# EEZ_DIB_DCP405_r2B5.net
KiCad netlist of a schematic drawn in EAGLE
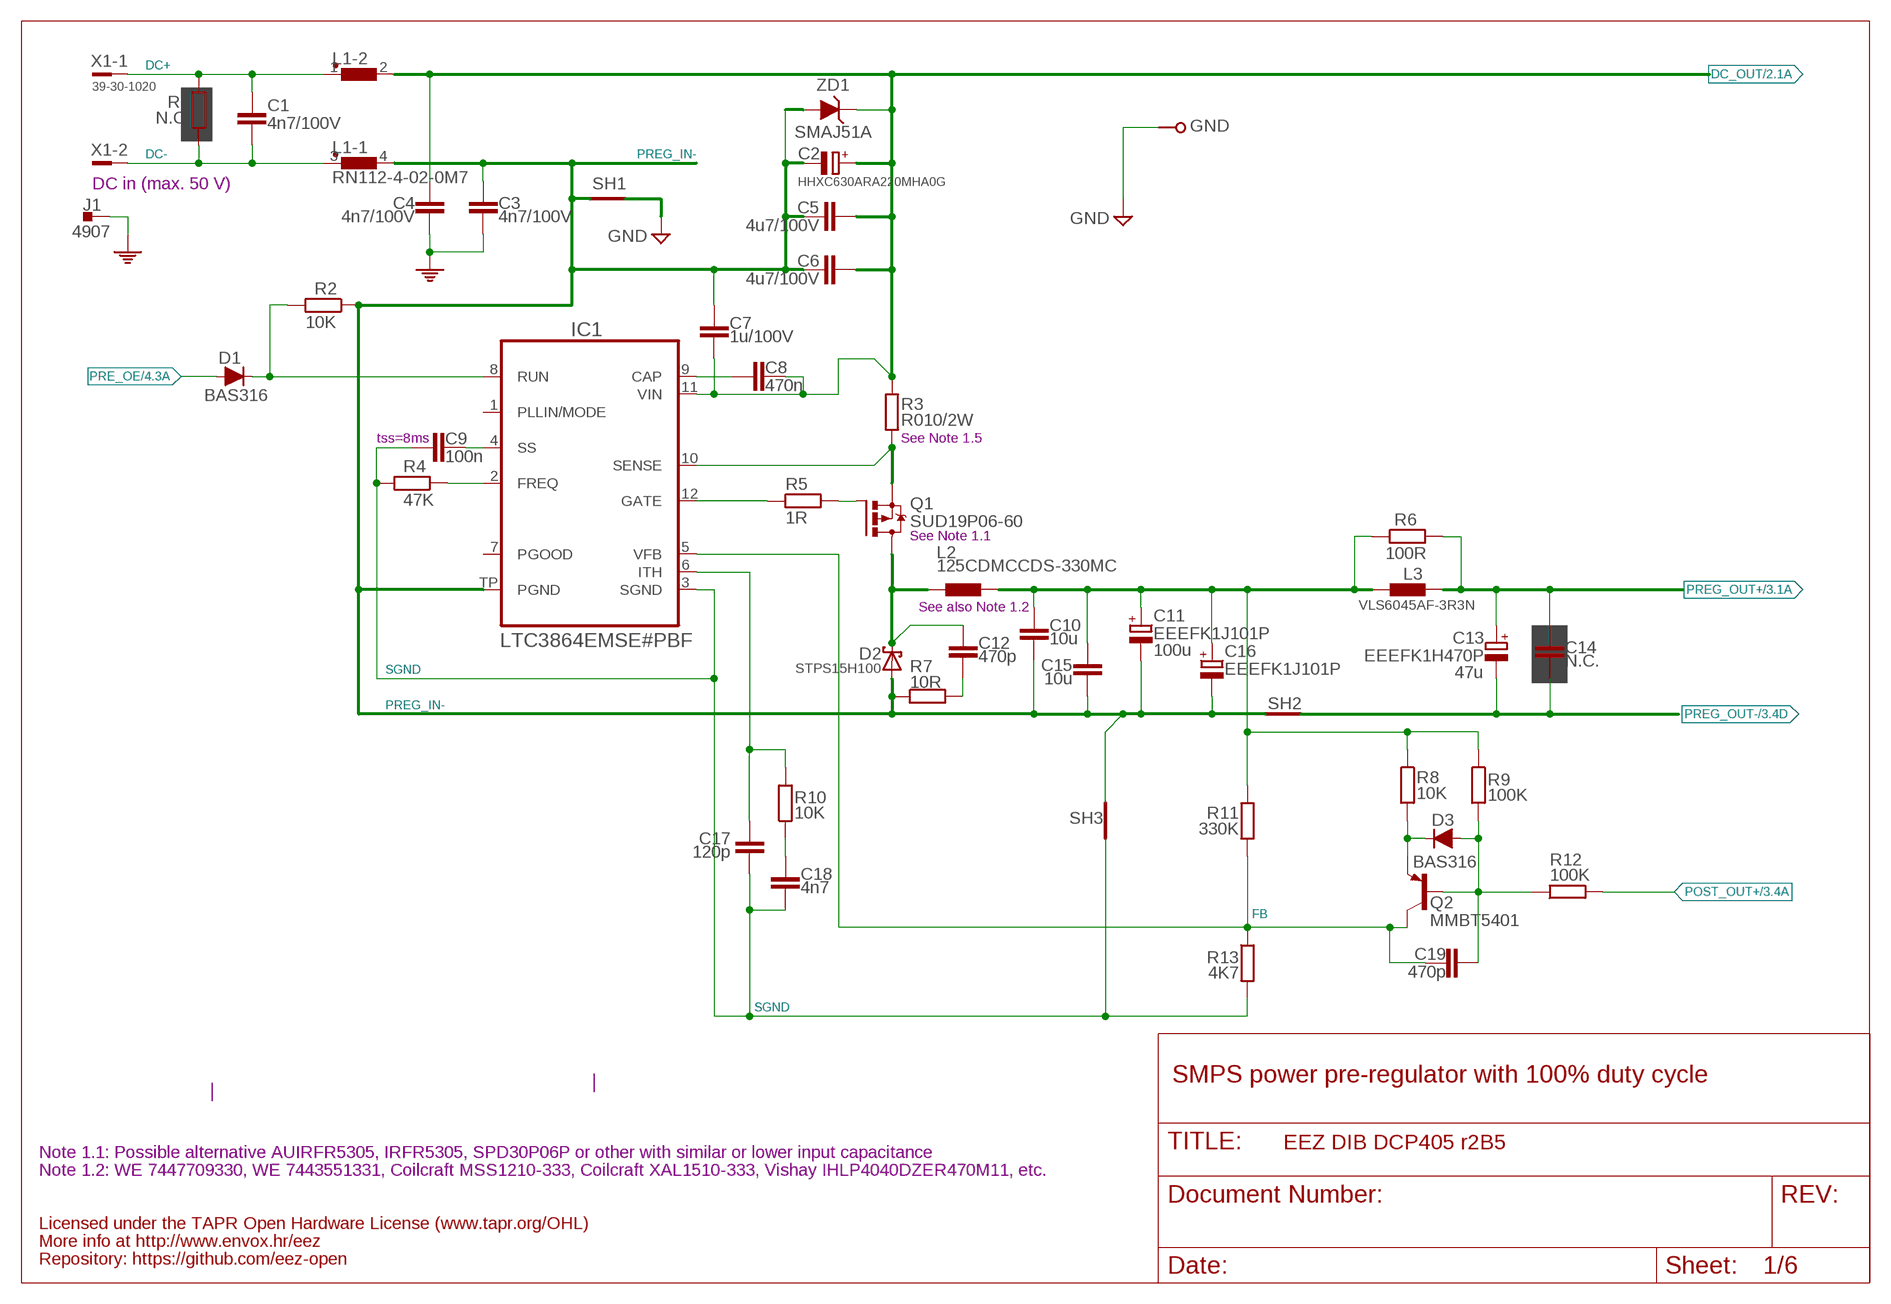
[diagram p0: schematic, sheet 1]
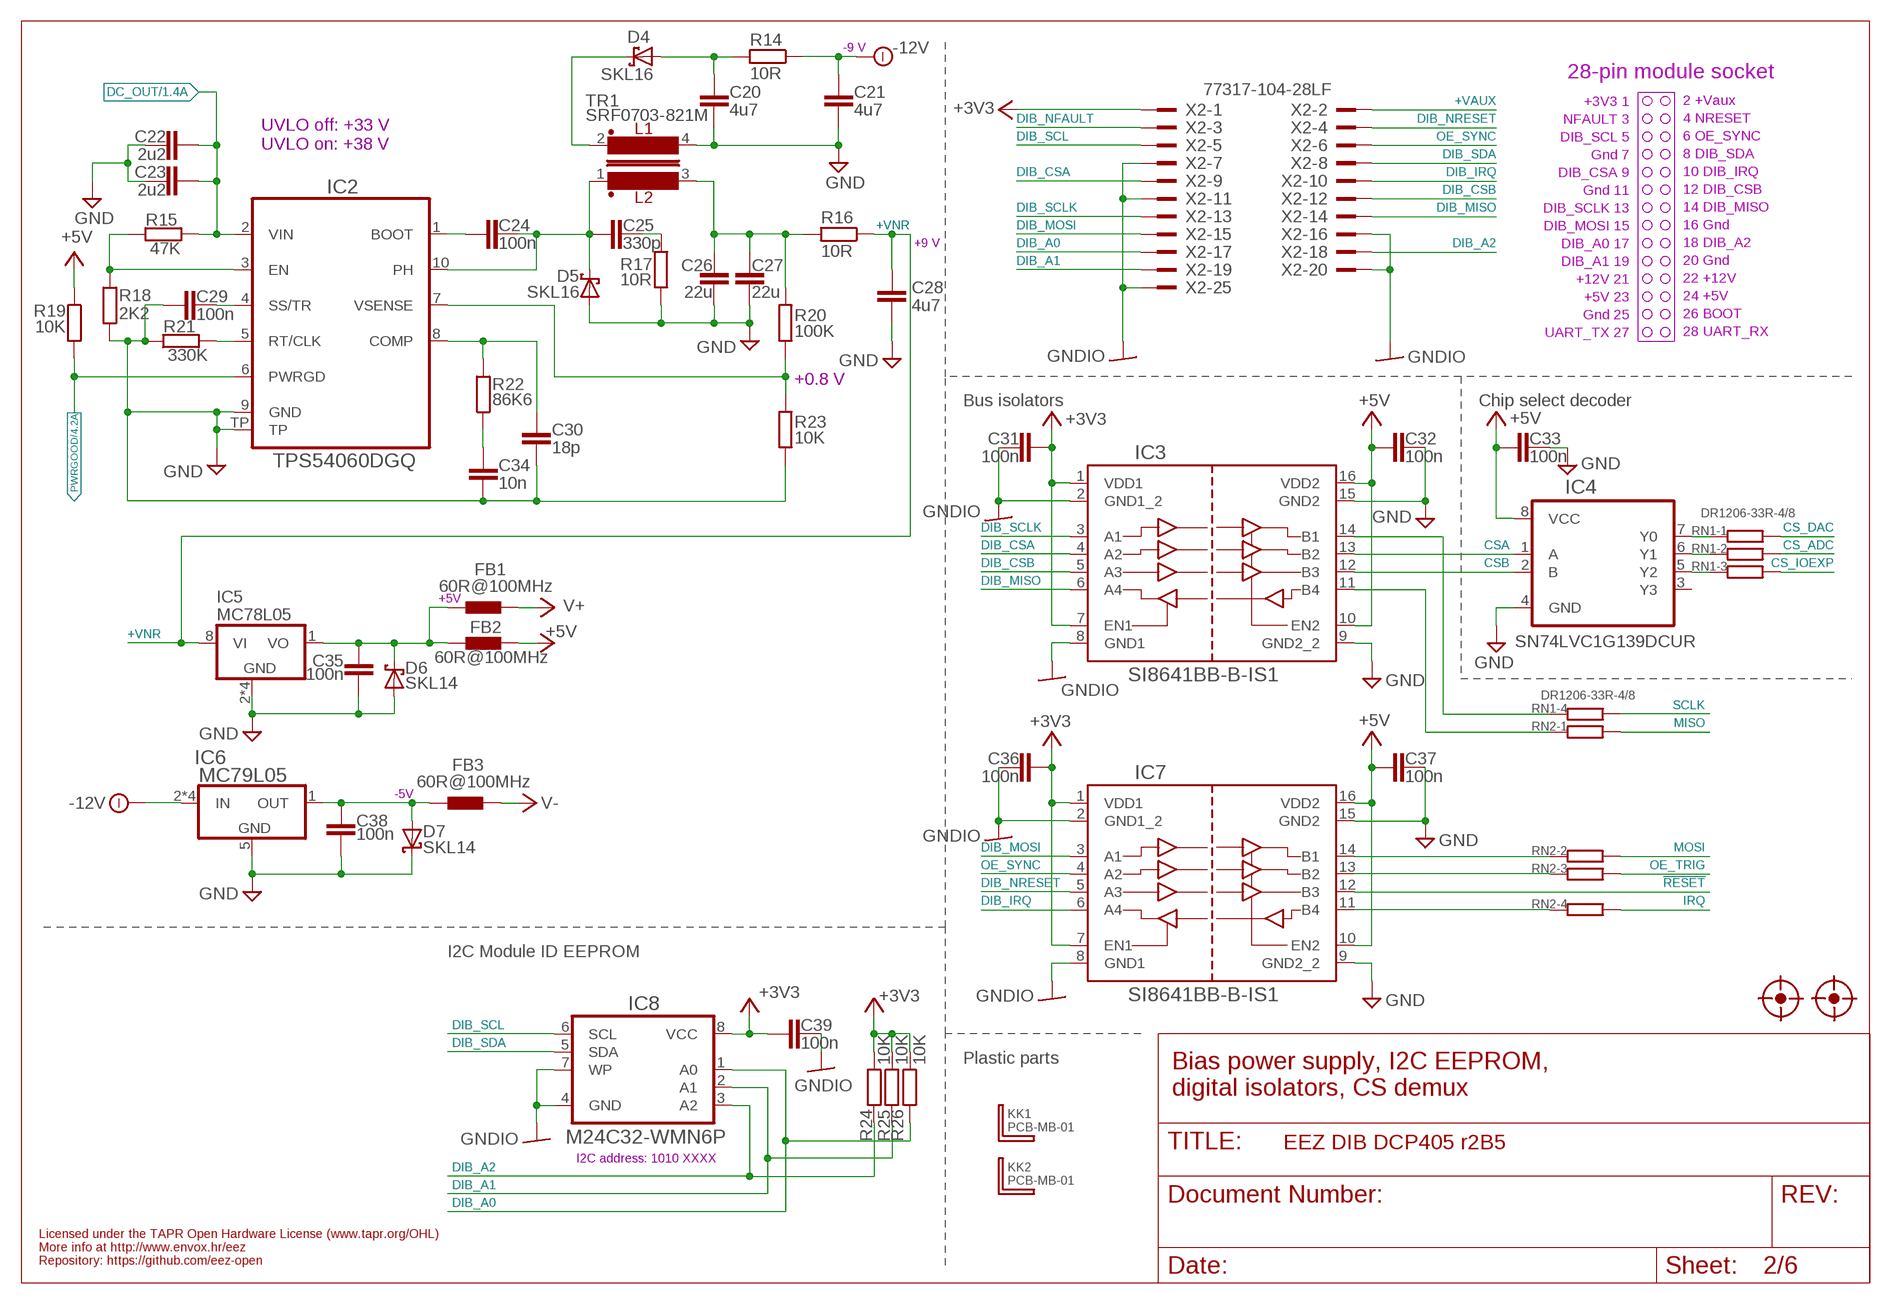
[diagram p1: schematic, sheet 2]
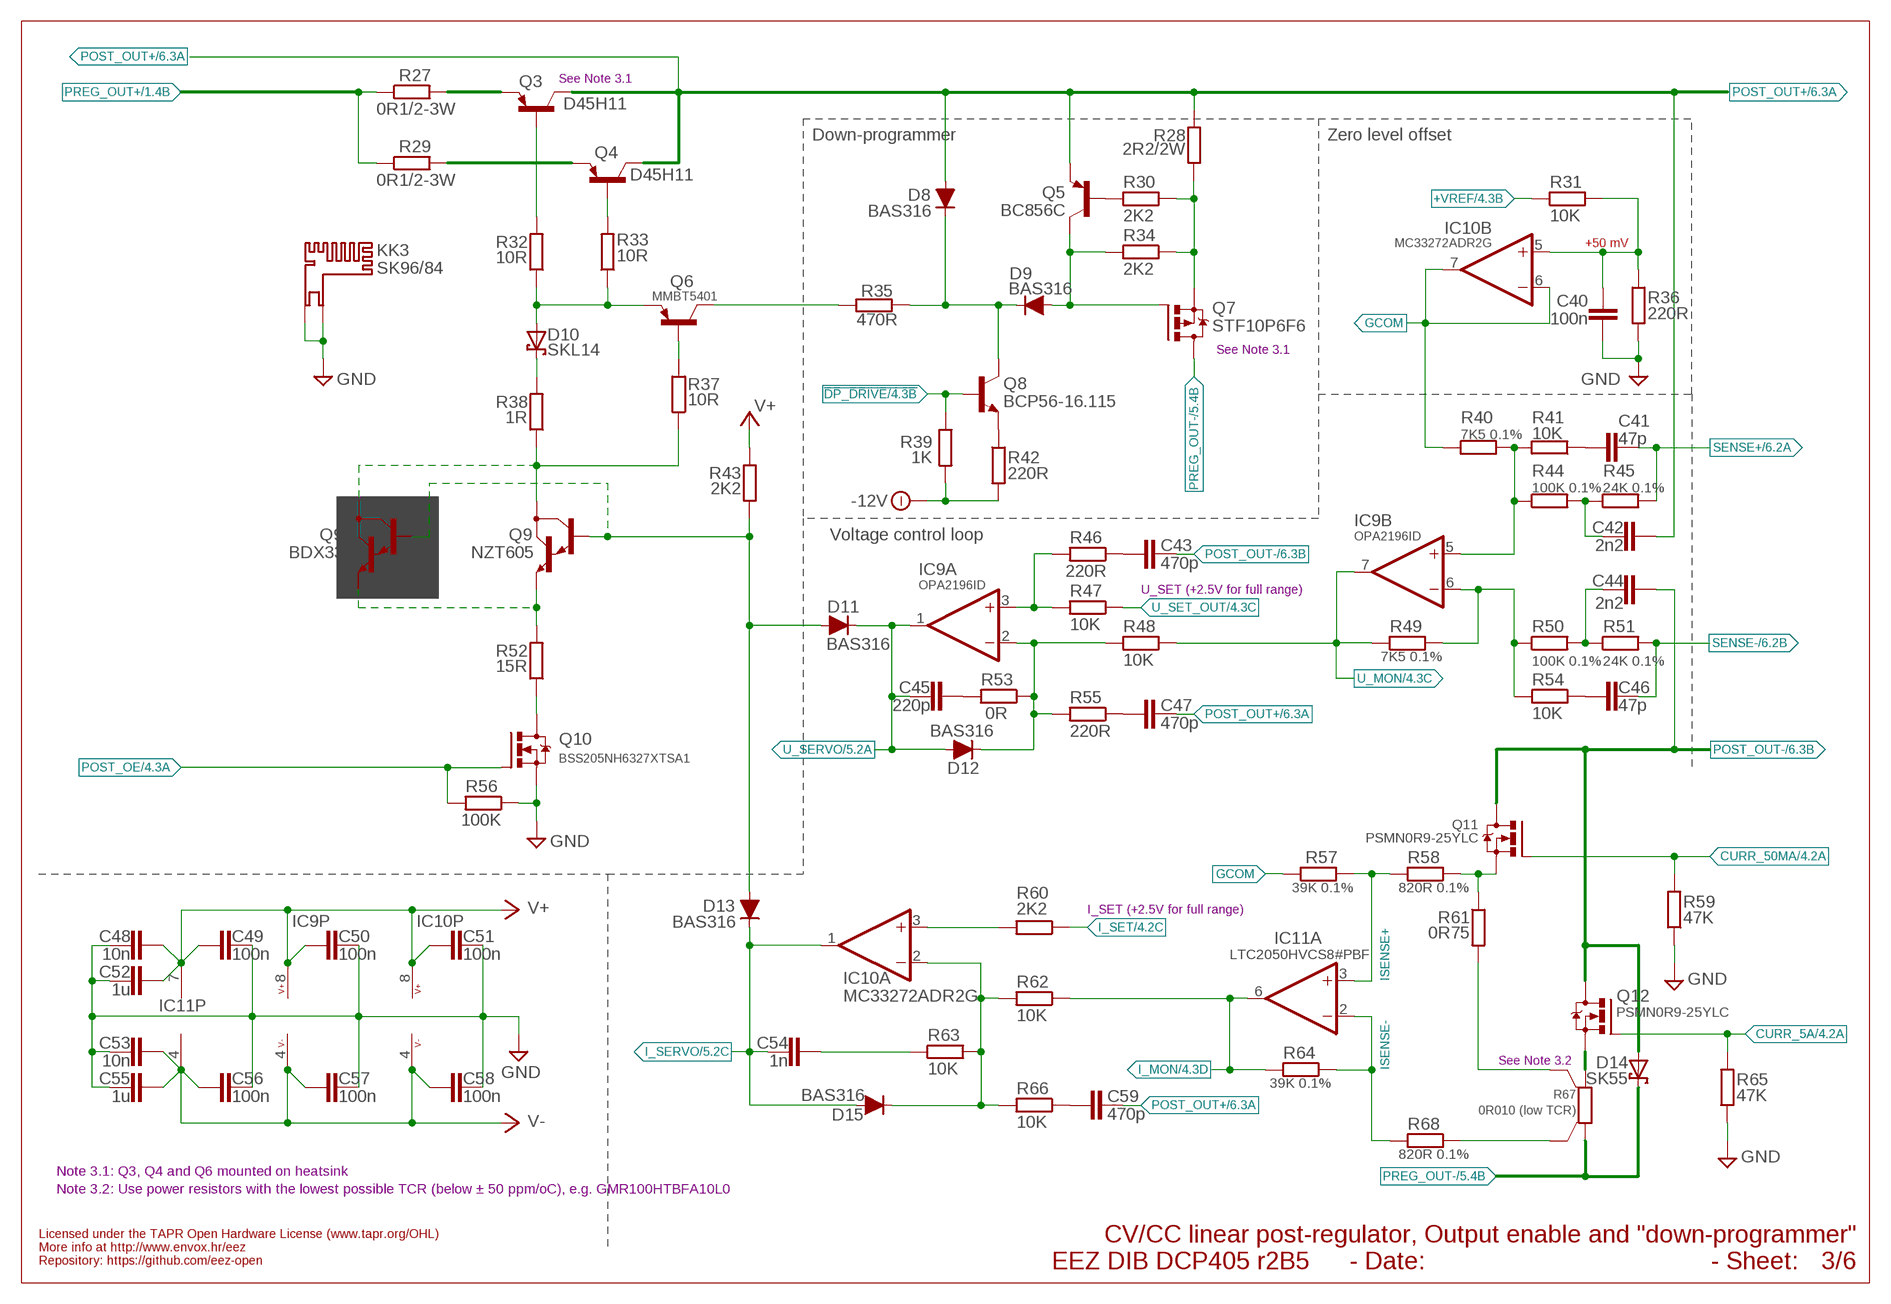
[diagram p2: schematic, sheet 3]
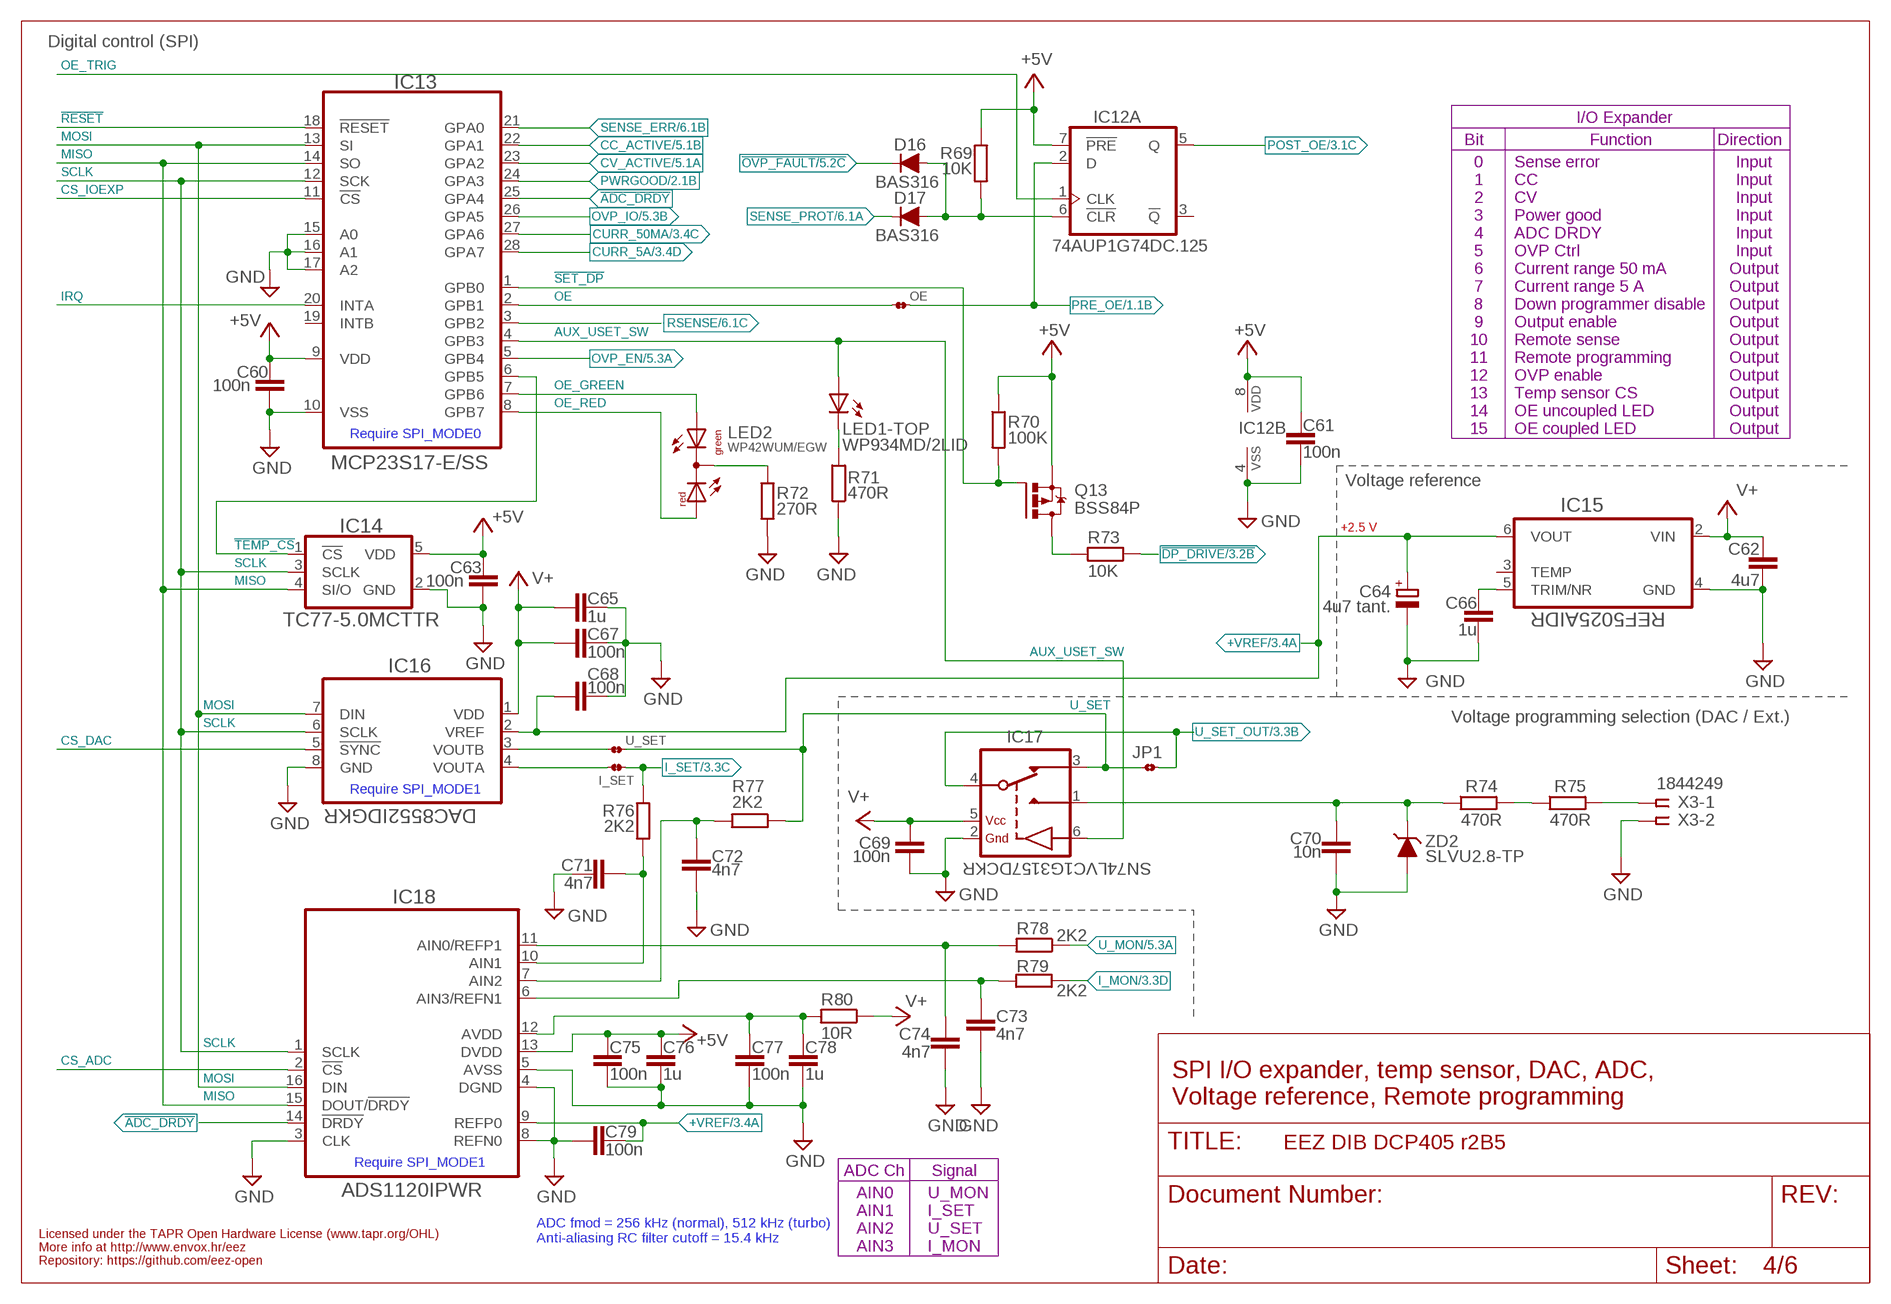
[diagram p3: schematic, sheet 4]
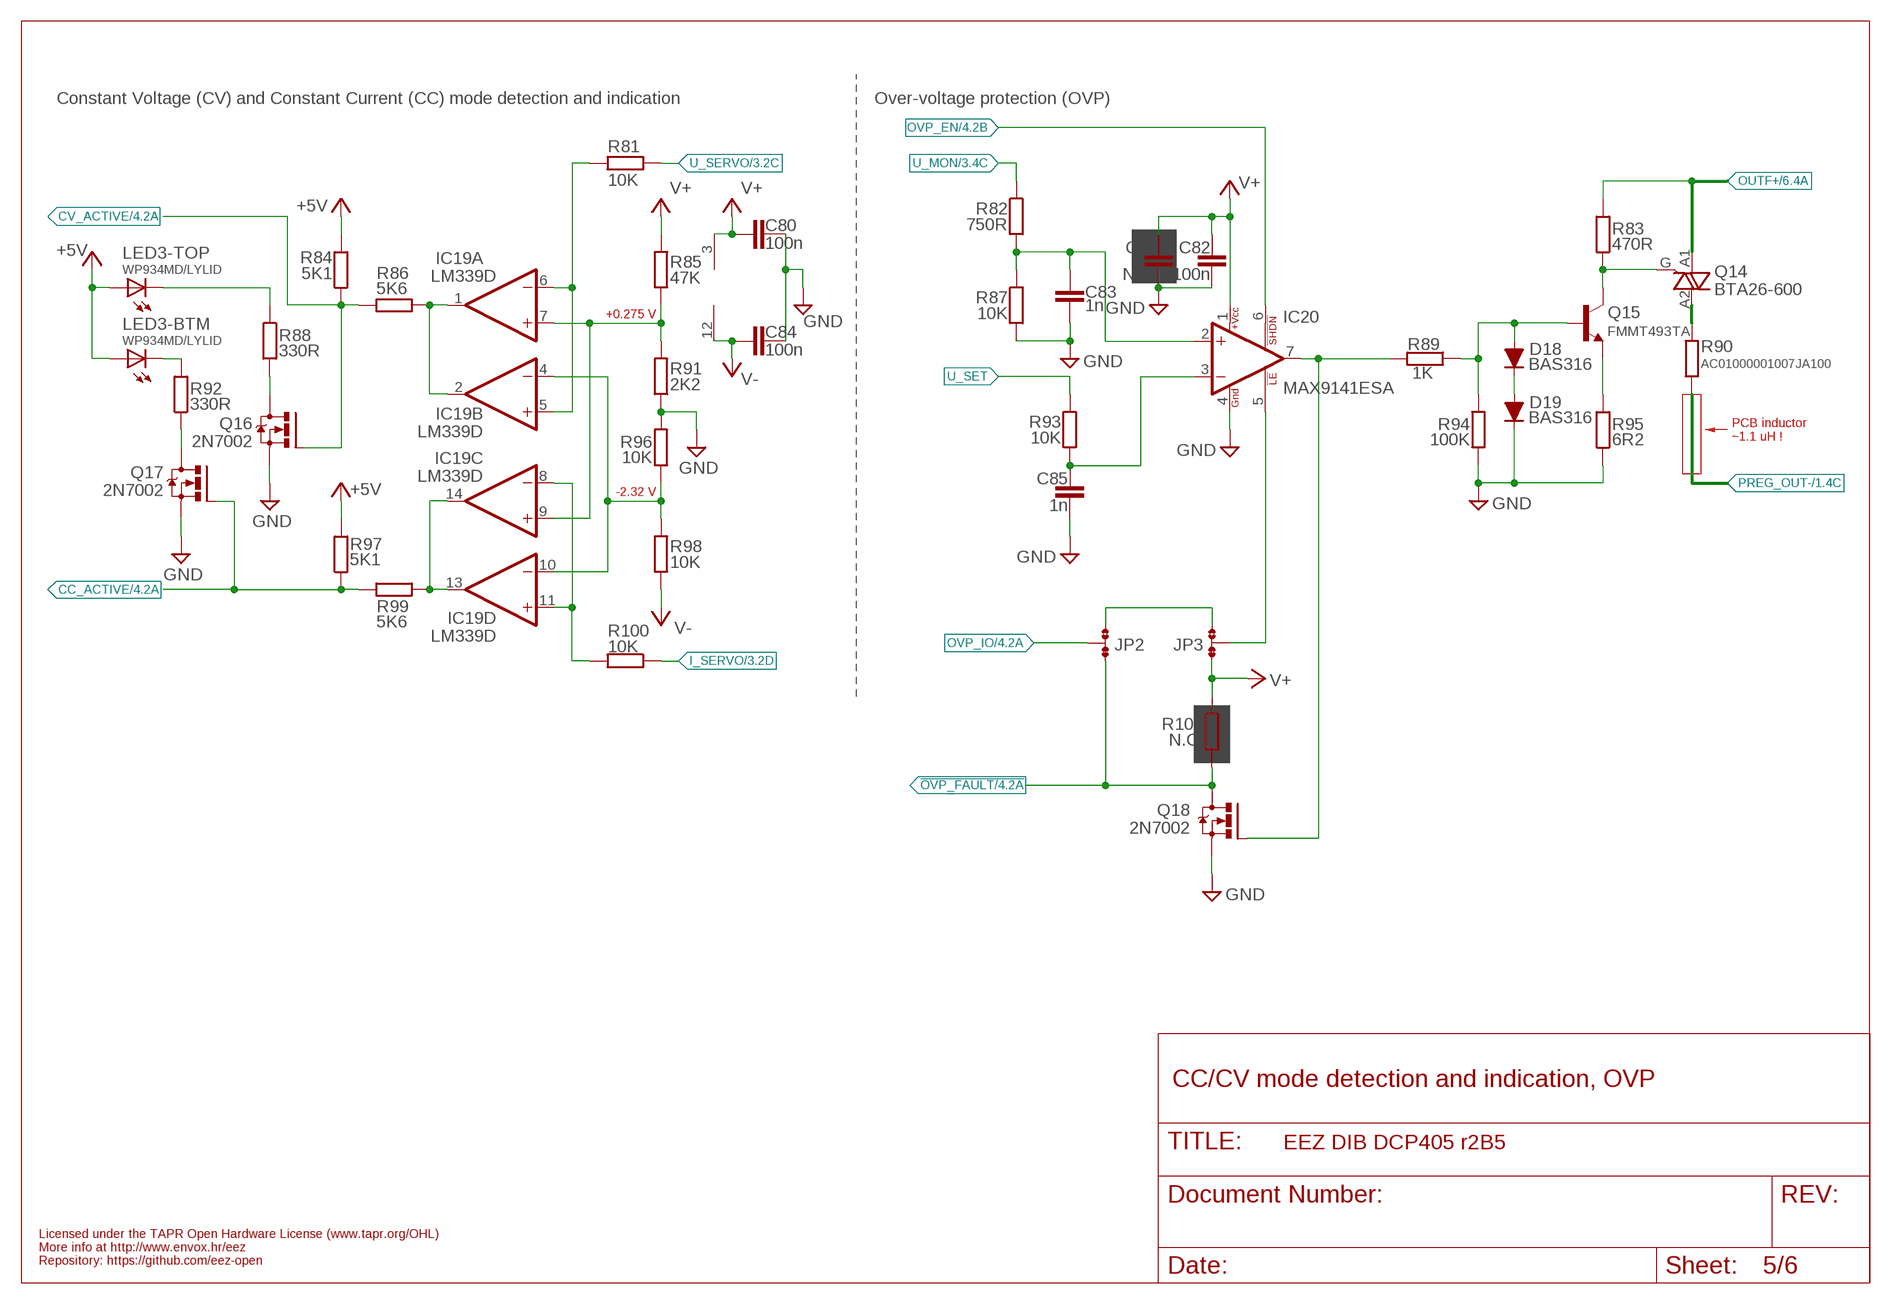
[diagram p4: schematic, sheet 5]
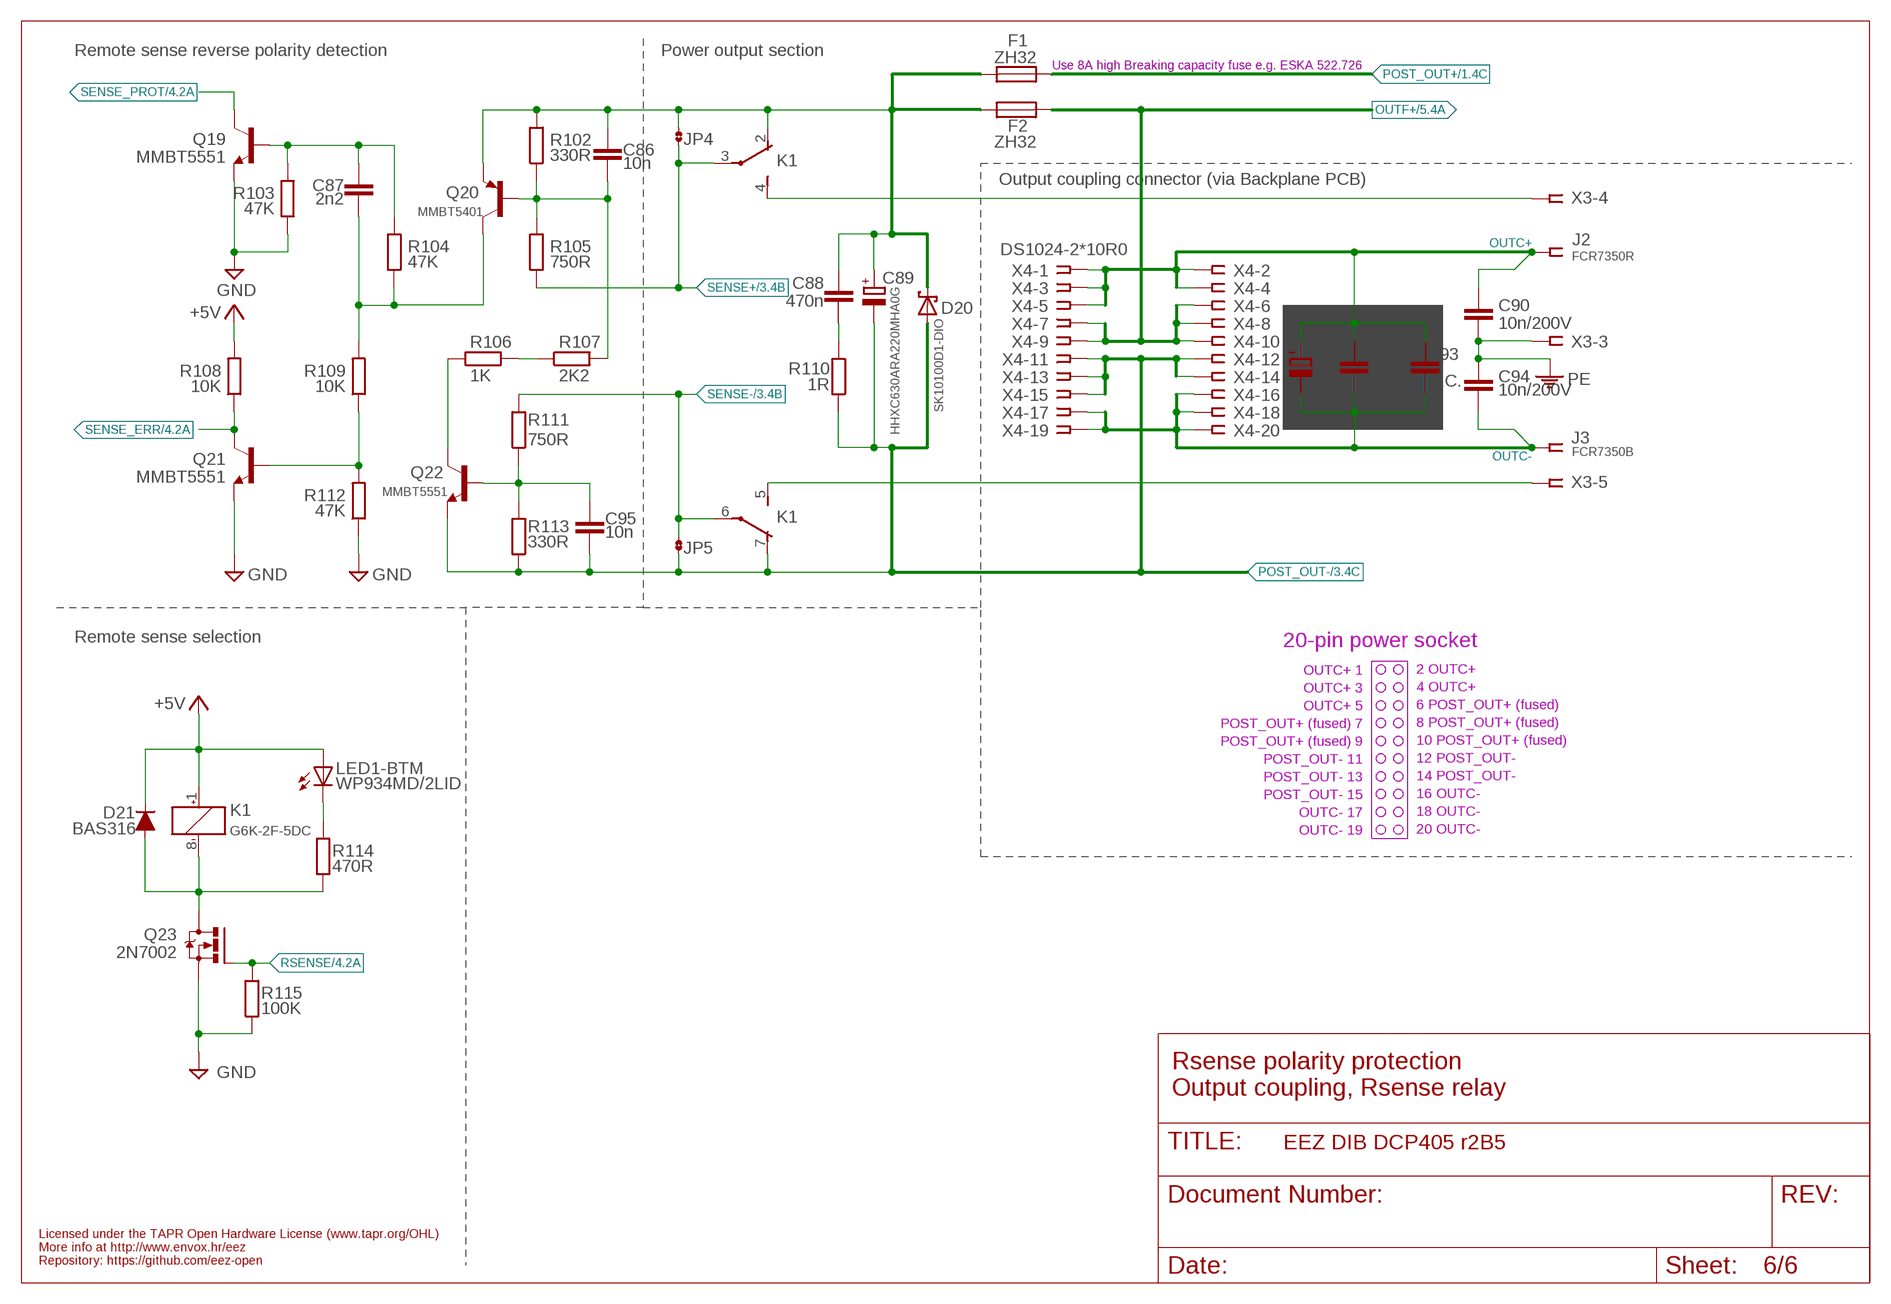
[diagram p5: schematic, sheet 6]

(export (version "E")
  (design (tool "Eeschema 10.0.6"))
  (components
    (comp (ref "C60")
      (value "100n")
      (footprint "eagle-import:C0603")
      (libsource (lib "eagle-import") (part "C-EUC0603"))
    )
    (comp (ref "C61")
      (value "100n")
      (footprint "eagle-import:C0603")
      (libsource (lib "eagle-import") (part "C-EUC0603"))
    )
    (comp (ref "C62")
      (value "4u7")
      (footprint "eagle-import:C1206")
      (libsource (lib "eagle-import") (part "C-EUC1206"))
    )
    (comp (ref "C63")
      (value "100n")
      (footprint "eagle-import:C0603")
      (libsource (lib "eagle-import") (part "C-EUC0603"))
    )
    (comp (ref "C64")
      (value "4u7 tant.")
      (footprint "eagle-import:EC1206")
      (libsource (lib "eagle-import") (part "ECAP1206"))
    )
    (comp (ref "C65")
      (value "1u")
      (footprint "eagle-import:C0805")
      (libsource (lib "eagle-import") (part "C-EUC0805"))
    )
    (comp (ref "C66")
      (value "1u")
      (footprint "eagle-import:C0805")
      (libsource (lib "eagle-import") (part "C-EUC0805"))
    )
    (comp (ref "C67")
      (value "100n")
      (footprint "eagle-import:C0603")
      (libsource (lib "eagle-import") (part "C-EUC0603"))
    )
    (comp (ref "C68")
      (value "100n")
      (footprint "eagle-import:C0603")
      (libsource (lib "eagle-import") (part "C-EUC0603"))
    )
    (comp (ref "C69")
      (value "100n")
      (footprint "eagle-import:C0603")
      (libsource (lib "eagle-import") (part "C-EUC0603"))
    )
    (comp (ref "C70")
      (value "10n")
      (footprint "eagle-import:C0805")
      (libsource (lib "eagle-import") (part "C-EUC0805"))
    )
    (comp (ref "C71")
      (value "4n7")
      (footprint "eagle-import:C0805")
      (libsource (lib "eagle-import") (part "C-EUC0805"))
    )
    (comp (ref "C72")
      (value "4n7")
      (footprint "eagle-import:C0805")
      (libsource (lib "eagle-import") (part "C-EUC0805"))
    )
    (comp (ref "C73")
      (value "4n7")
      (footprint "eagle-import:C0805")
      (libsource (lib "eagle-import") (part "C-EUC0805"))
    )
    (comp (ref "C74")
      (value "4n7")
      (footprint "eagle-import:C0805")
      (libsource (lib "eagle-import") (part "C-EUC0805"))
    )
    (comp (ref "C75")
      (value "100n")
      (footprint "eagle-import:C0603")
      (libsource (lib "eagle-import") (part "C-EUC0603"))
    )
    (comp (ref "C76")
      (value "1u")
      (footprint "eagle-import:C0805")
      (libsource (lib "eagle-import") (part "C-EUC0805"))
    )
    (comp (ref "C77")
      (value "100n")
      (footprint "eagle-import:C0603")
      (libsource (lib "eagle-import") (part "C-EUC0603"))
    )
    (comp (ref "C78")
      (value "1u")
      (footprint "eagle-import:C0805")
      (libsource (lib "eagle-import") (part "C-EUC0805"))
    )
    (comp (ref "C79")
      (value "100n")
      (footprint "eagle-import:C0603")
      (libsource (lib "eagle-import") (part "C-EUC0603"))
    )
    (comp (ref "D16")
      (value "BAS316")
      (footprint "eagle-import:SOD323-R")
      (libsource (lib "eagle-import") (part "DIODESOD323R"))
    )
    (comp (ref "D17")
      (value "BAS316")
      (footprint "eagle-import:SOD323-R")
      (libsource (lib "eagle-import") (part "DIODESOD323R"))
    )
    (comp (ref "IC12")
      (value "74AUP1G74DC.125")
      (footprint "eagle-import:DCU8")
      (libsource (lib "eagle-import") (part "SN74LVC1G74DCTR-VSSOP"))
    )
    (comp (ref "IC13")
      (value "MCP23S17-E/SS")
      (footprint "eagle-import:SOP65P780X200-28N")
      (libsource (lib "eagle-import") (part "MCP23S17-E/SSSSOP"))
    )
    (comp (ref "IC14")
      (value "TC77-5.0MCTTR")
      (footprint "eagle-import:SOT23-5")
      (libsource (lib "eagle-import") (part "TC77"))
    )
    (comp (ref "IC15")
      (value "REF5025AIDR")
      (footprint "eagle-import:SOIC127P600X175-8N")
      (libsource (lib "eagle-import") (part "REF50XX"))
    )
    (comp (ref "IC16")
      (value "DAC8552IDGKR")
      (footprint "eagle-import:DGK8-M")
      (libsource (lib "eagle-import") (part "DAC8552_DGK_8M"))
    )
    (comp (ref "IC17")
      (value "SN74LVC1G3157DCKR")
      (footprint "eagle-import:SOT65P210X110-6N")
      (libsource (lib "eagle-import") (part "SN74LVC1G3157-DCK"))
    )
    (comp (ref "IC18")
      (value "ADS1120IPWR")
      (footprint "eagle-import:PW(R-PDSO-G16)")
      (libsource (lib "eagle-import") (part "ADS1120TSSOP-16"))
    )
    (comp (ref "I_SET")
      (value "JP2-NOCUT")
      (footprint "eagle-import:JP2-NOCUT")
      (libsource (lib "eagle-import") (part "JP2-NOCUT"))
    )
    (comp (ref "JP1")
      (value "JP2-CUT")
      (footprint "eagle-import:JP2-CUT")
      (libsource (lib "eagle-import") (part "JP2-CUT"))
    )
    (comp (ref "LED1")
      (value "WP934MD/2LID")
      (footprint "eagle-import:WP934MD")
      (libsource (lib "eagle-import") (part "WP934MD/2LID"))
    )
    (comp (ref "LED2")
      (value "WP42WUM/EGW")
      (footprint "eagle-import:L-42WUM-1EGWT")
      (libsource (lib "eagle-import") (part "LED_L-42WUM/1EGWT"))
    )
    (comp (ref "OE")
      (value "JP2-NOCUT")
      (footprint "eagle-import:JP2-NOCUT")
      (libsource (lib "eagle-import") (part "JP2-NOCUT"))
    )
    (comp (ref "Q13")
      (value "BSS84P")
      (footprint "eagle-import:SOT95P237X112-3N")
      (fields (field (name "MPN") "IRLML2246TRPBF"))
      (libsource (lib "eagle-import") (part "IRLML2246TRPBF"))
    )
    (comp (ref "R69")
      (value "10K")
      (footprint "eagle-import:R0805")
      (libsource (lib "eagle-import") (part "R-EU_R0805"))
    )
    (comp (ref "R70")
      (value "100K")
      (footprint "eagle-import:R0805")
      (libsource (lib "eagle-import") (part "R-EU_R0805"))
    )
    (comp (ref "R71")
      (value "470R")
      (footprint "eagle-import:R0805")
      (libsource (lib "eagle-import") (part "R-EU_R0805"))
    )
    (comp (ref "R72")
      (value "270R")
      (footprint "eagle-import:R0805")
      (libsource (lib "eagle-import") (part "R-EU_R0805"))
    )
    (comp (ref "R73")
      (value "10K")
      (footprint "eagle-import:R0805")
      (libsource (lib "eagle-import") (part "R-EU_R0805"))
    )
    (comp (ref "R74")
      (value "470R")
      (footprint "eagle-import:R0805")
      (libsource (lib "eagle-import") (part "R-EU_R0805"))
    )
    (comp (ref "R75")
      (value "470R")
      (footprint "eagle-import:R0805")
      (libsource (lib "eagle-import") (part "R-EU_R0805"))
    )
    (comp (ref "R76")
      (value "2K2")
      (footprint "eagle-import:R0805")
      (libsource (lib "eagle-import") (part "R-EU_R0805"))
    )
    (comp (ref "R77")
      (value "2K2")
      (footprint "eagle-import:R0805")
      (libsource (lib "eagle-import") (part "R-EU_R0805"))
    )
    (comp (ref "R78")
      (value "2K2")
      (footprint "eagle-import:R0805")
      (libsource (lib "eagle-import") (part "R-EU_R0805"))
    )
    (comp (ref "R79")
      (value "2K2")
      (footprint "eagle-import:R0805")
      (libsource (lib "eagle-import") (part "R-EU_R0805"))
    )
    (comp (ref "R80")
      (value "10R")
      (footprint "eagle-import:R1206")
      (libsource (lib "eagle-import") (part "R-EU_R1206"))
    )
    (comp (ref "U_SET")
      (value "JP2-NOCUT")
      (footprint "eagle-import:JP2-NOCUT")
      (libsource (lib "eagle-import") (part "JP2-NOCUT"))
    )
    (comp (ref "X3")
      (value "1844249")
      (footprint "eagle-import:MC1,5_5-G-3,5")
      (libsource (lib "eagle-import") (part "MC1,5/5-G-3,5"))
    )
    (comp (ref "ZD2")
      (value "SLVU2.8-TP")
      (footprint "eagle-import:SOT23")
      (libsource (lib "eagle-import") (part "SLVU2.8"))
    )
    (comp (ref "C1")
      (value "4n7/100V")
      (footprint "eagle-import:C1206")
      (libsource (lib "eagle-import") (part "C-EUC1206"))
    )
    (comp (ref "C2")
      (value "HHXC630ARA220MHA0G")
      (footprint "eagle-import:CAPAE830X1050N")
      (libsource (lib "eagle-import") (part "ECAPSMD8.3MM/HA0"))
    )
    (comp (ref "C3")
      (value "4n7/100V")
      (footprint "eagle-import:C1206")
      (libsource (lib "eagle-import") (part "C-EUC1206"))
    )
    (comp (ref "C4")
      (value "4n7/100V")
      (footprint "eagle-import:C1206")
      (libsource (lib "eagle-import") (part "C-EUC1206"))
    )
    (comp (ref "C5")
      (value "4u7/100V")
      (footprint "eagle-import:C1210")
      (libsource (lib "eagle-import") (part "C-EUC1210"))
    )
    (comp (ref "C6")
      (value "4u7/100V")
      (footprint "eagle-import:C1210")
      (libsource (lib "eagle-import") (part "C-EUC1210"))
    )
    (comp (ref "C7")
      (value "1u/100V")
      (footprint "eagle-import:C1206")
      (libsource (lib "eagle-import") (part "C-EUC1206"))
    )
    (comp (ref "C8")
      (value "470n")
      (footprint "eagle-import:C0805")
      (libsource (lib "eagle-import") (part "C-EUC0805"))
    )
    (comp (ref "C9")
      (value "100n")
      (footprint "eagle-import:C0603")
      (libsource (lib "eagle-import") (part "C-EUC0603"))
    )
    (comp (ref "C10")
      (value "10u")
      (footprint "eagle-import:C1210")
      (libsource (lib "eagle-import") (part "C-EUC1210"))
    )
    (comp (ref "C11")
      (value "EEEFK1J101P")
      (footprint "eagle-import:CAPAE1030X1050N")
      (libsource (lib "eagle-import") (part "ECAP10X10"))
    )
    (comp (ref "C12")
      (value "470p")
      (footprint "eagle-import:C0805")
      (libsource (lib "eagle-import") (part "C-EUC0805"))
    )
    (comp (ref "C13")
      (value "EEEFK1H470P")
      (footprint "eagle-import:CAPAE830X1050N")
      (libsource (lib "eagle-import") (part "ECAPSMD8.3MM/HA0"))
    )
    (comp (ref "C14")
      (value "N.C.")
      (footprint "eagle-import:C0805")
      (libsource (lib "eagle-import") (part "C-EUC0805"))
    )
    (comp (ref "C15")
      (value "10u")
      (footprint "eagle-import:C1210")
      (libsource (lib "eagle-import") (part "C-EUC1210"))
    )
    (comp (ref "C16")
      (value "EEEFK1J101P")
      (footprint "eagle-import:CAPAE1030X1050N")
      (libsource (lib "eagle-import") (part "ECAP10X10"))
    )
    (comp (ref "C17")
      (value "120p")
      (footprint "eagle-import:C0805")
      (libsource (lib "eagle-import") (part "C-EUC0805"))
    )
    (comp (ref "C18")
      (value "4n7")
      (footprint "eagle-import:C0805")
      (libsource (lib "eagle-import") (part "C-EUC0805"))
    )
    (comp (ref "C19")
      (value "470p")
      (footprint "eagle-import:C0805")
      (libsource (lib "eagle-import") (part "C-EUC0805"))
    )
    (comp (ref "D1")
      (value "BAS316")
      (footprint "eagle-import:SOD323-R")
      (libsource (lib "eagle-import") (part "DIODESOD323R"))
    )
    (comp (ref "D2")
      (value "STPS15H100")
      (footprint "eagle-import:TO252-L")
      (libsource (lib "eagle-import") (part "SCHOTTKY-DUAL_A_L"))
    )
    (comp (ref "D3")
      (value "BAS316")
      (footprint "eagle-import:SOD323-R")
      (libsource (lib "eagle-import") (part "DIODESOD323R"))
    )
    (comp (ref "GND")
      (value "PCB_TEST_TABSHIELD")
      (footprint "eagle-import:PCB_SHIELD_TAB")
      (libsource (lib "eagle-import") (part "PCB_TEST_TABSHIELD"))
    )
    (comp (ref "IC1")
      (value "LTC3864EMSE#PBF")
      (footprint "eagle-import:LTC_05-08-1666")
      (libsource (lib "eagle-import") (part "LTC3864"))
    )
    (comp (ref "J1")
      (value "4907")
      (footprint "eagle-import:PCB_TAB-4907")
      (libsource (lib "eagle-import") (part "PCB_TAB-4907"))
    )
    (comp (ref "L1")
      (value "RN112-4-02-0M7")
      (footprint "eagle-import:RN112")
      (libsource (lib "eagle-import") (part "RN112"))
    )
    (comp (ref "L2")
      (value "125CDMCCDS-330MC")
      (footprint "eagle-import:125CDMCC_DS")
      (libsource (lib "eagle-import") (part "125CDMCC/DS"))
    )
    (comp (ref "L3")
      (value "VLS6045AF-3R3N")
      (footprint "eagle-import:COILCRAFT_HPI0630")
      (libsource (lib "eagle-import") (part "COILCRAFT_HPI0630"))
    )
    (comp (ref "Q1")
      (value "SUD19P06-60")
      (footprint "eagle-import:TO229P990X239-3N")
      (libsource (lib "eagle-import") (part "P-MOSFETDPAK"))
    )
    (comp (ref "Q2")
      (value "MMBT5401")
      (footprint "eagle-import:SOT23-BEC")
      (libsource (lib "eagle-import") (part "-PNP-SOT23-BECBC857B"))
    )
    (comp (ref "R1")
      (value "N.C.")
      (footprint "eagle-import:R2512")
      (libsource (lib "eagle-import") (part "R-EU_R2512"))
    )
    (comp (ref "R2")
      (value "10K")
      (footprint "eagle-import:R0805")
      (libsource (lib "eagle-import") (part "R-EU_R0805"))
    )
    (comp (ref "R3")
      (value "R010/2W")
      (footprint "eagle-import:R2512")
      (libsource (lib "eagle-import") (part "R-EU_R2512"))
    )
    (comp (ref "R4")
      (value "47K")
      (footprint "eagle-import:R0805")
      (libsource (lib "eagle-import") (part "R-EU_R0805"))
    )
    (comp (ref "R5")
      (value "1R")
      (footprint "eagle-import:R0805")
      (libsource (lib "eagle-import") (part "R-EU_R0805"))
    )
    (comp (ref "R6")
      (value "100R")
      (footprint "eagle-import:R0805")
      (libsource (lib "eagle-import") (part "R-EU_R0805"))
    )
    (comp (ref "R7")
      (value "10R")
      (footprint "eagle-import:R1206")
      (libsource (lib "eagle-import") (part "R-EU_R1206"))
    )
    (comp (ref "R8")
      (value "10K")
      (footprint "eagle-import:R0805")
      (libsource (lib "eagle-import") (part "R-EU_R0805"))
    )
    (comp (ref "R9")
      (value "100K")
      (footprint "eagle-import:R0805")
      (libsource (lib "eagle-import") (part "R-EU_R0805"))
    )
    (comp (ref "R10")
      (value "10K")
      (footprint "eagle-import:R0805")
      (libsource (lib "eagle-import") (part "R-EU_R0805"))
    )
    (comp (ref "R11")
      (value "330K")
      (footprint "eagle-import:R0805")
      (libsource (lib "eagle-import") (part "R-EU_R0805"))
    )
    (comp (ref "R12")
      (value "100K")
      (footprint "eagle-import:R0805")
      (libsource (lib "eagle-import") (part "R-EU_R0805"))
    )
    (comp (ref "R13")
      (value "4K7")
      (footprint "eagle-import:R0805")
      (libsource (lib "eagle-import") (part "R-EU_R0805"))
    )
    (comp (ref "SH1")
      (value "SHORTNOHOLE")
      (footprint "eagle-import:SHORT_NOHOLE")
      (libsource (lib "eagle-import") (part "SHORTNOHOLE"))
    )
    (comp (ref "SH2")
      (value "Pgnd to Pout- short")
      (footprint "eagle-import:SHORT_NOHOLE")
      (libsource (lib "eagle-import") (part "SHORTNOHOLE"))
    )
    (comp (ref "SH3")
      (value "Sgnd to Pgnd short")
      (footprint "eagle-import:SHORT_NOHOLE")
      (libsource (lib "eagle-import") (part "SHORTNOHOLE"))
    )
    (comp (ref "X1")
      (value "39-30-1020")
      (footprint "eagle-import:MINIFIT_39301020")
      (libsource (lib "eagle-import") (part "MINIFIT_39301020"))
    )
    (comp (ref "ZD1")
      (value "SMAJ51A")
      (footprint "eagle-import:DO214AA")
      (libsource (lib "eagle-import") (part "P6SMB68A"))
    )
    (comp (ref "C40")
      (value "100n")
      (footprint "eagle-import:C0603")
      (libsource (lib "eagle-import") (part "C-EUC0603"))
    )
    (comp (ref "C41")
      (value "47p")
      (footprint "eagle-import:C0805")
      (libsource (lib "eagle-import") (part "C-EUC0805"))
    )
    (comp (ref "C42")
      (value "2n2")
      (footprint "eagle-import:C0805")
      (libsource (lib "eagle-import") (part "C-EUC0805"))
    )
    (comp (ref "C43")
      (value "470p")
      (footprint "eagle-import:C0805")
      (libsource (lib "eagle-import") (part "C-EUC0805"))
    )
    (comp (ref "C44")
      (value "2n2")
      (footprint "eagle-import:C0805")
      (libsource (lib "eagle-import") (part "C-EUC0805"))
    )
    (comp (ref "C45")
      (value "220p")
      (footprint "eagle-import:C0805")
      (libsource (lib "eagle-import") (part "C-EUC0805"))
    )
    (comp (ref "C46")
      (value "47p")
      (footprint "eagle-import:C0805")
      (libsource (lib "eagle-import") (part "C-EUC0805"))
    )
    (comp (ref "C47")
      (value "470p")
      (footprint "eagle-import:C0805")
      (libsource (lib "eagle-import") (part "C-EUC0805"))
    )
    (comp (ref "C48")
      (value "10n")
      (footprint "eagle-import:C0805")
      (libsource (lib "eagle-import") (part "C-EUC0805"))
    )
    (comp (ref "C49")
      (value "100n")
      (footprint "eagle-import:C0603")
      (libsource (lib "eagle-import") (part "C-EUC0603"))
    )
    (comp (ref "C50")
      (value "100n")
      (footprint "eagle-import:C0603")
      (libsource (lib "eagle-import") (part "C-EUC0603"))
    )
    (comp (ref "C51")
      (value "100n")
      (footprint "eagle-import:C0603")
      (libsource (lib "eagle-import") (part "C-EUC0603"))
    )
    (comp (ref "C52")
      (value "1u")
      (footprint "eagle-import:C0805")
      (libsource (lib "eagle-import") (part "C-EUC0805"))
    )
    (comp (ref "C53")
      (value "10n")
      (footprint "eagle-import:C0805")
      (libsource (lib "eagle-import") (part "C-EUC0805"))
    )
    (comp (ref "C54")
      (value "1n")
      (footprint "eagle-import:C0805")
      (libsource (lib "eagle-import") (part "C-EUC0805"))
    )
    (comp (ref "C55")
      (value "1u")
      (footprint "eagle-import:C0805")
      (libsource (lib "eagle-import") (part "C-EUC0805"))
    )
    (comp (ref "C56")
      (value "100n")
      (footprint "eagle-import:C0603")
      (libsource (lib "eagle-import") (part "C-EUC0603"))
    )
    (comp (ref "C57")
      (value "100n")
      (footprint "eagle-import:C0603")
      (libsource (lib "eagle-import") (part "C-EUC0603"))
    )
    (comp (ref "C58")
      (value "100n")
      (footprint "eagle-import:C0603")
      (libsource (lib "eagle-import") (part "C-EUC0603"))
    )
    (comp (ref "C59")
      (value "470p")
      (footprint "eagle-import:C0805")
      (libsource (lib "eagle-import") (part "C-EUC0805"))
    )
    (comp (ref "D8")
      (value "BAS316")
      (footprint "eagle-import:SOD323-R")
      (libsource (lib "eagle-import") (part "DIODESOD323R"))
    )
    (comp (ref "D9")
      (value "BAS316")
      (footprint "eagle-import:SOD323-R")
      (libsource (lib "eagle-import") (part "DIODESOD323R"))
    )
    (comp (ref "D10")
      (value "SKL14")
      (footprint "eagle-import:SOD123")
      (libsource (lib "eagle-import") (part "SCHOTTKYSOD123"))
    )
    (comp (ref "D11")
      (value "BAS316")
      (footprint "eagle-import:SOD323-R")
      (libsource (lib "eagle-import") (part "DIODESOD323R"))
    )
    (comp (ref "D12")
      (value "BAS316")
      (footprint "eagle-import:SOD323-R")
      (libsource (lib "eagle-import") (part "DIODESOD323R"))
    )
    (comp (ref "D13")
      (value "BAS316")
      (footprint "eagle-import:SOD323-R")
      (libsource (lib "eagle-import") (part "DIODESOD323R"))
    )
    (comp (ref "D14")
      (value "SK55")
      (footprint "eagle-import:SMB")
      (libsource (lib "eagle-import") (part "SCHOTTKYSMB"))
    )
    (comp (ref "D15")
      (value "BAS316")
      (footprint "eagle-import:SOD323-R")
      (libsource (lib "eagle-import") (part "DIODESOD323R"))
    )
    (comp (ref "IC9")
      (value "OPA2196ID")
      (footprint "eagle-import:SOIC127P600X173-8N")
      (libsource (lib "eagle-import") (part "TL072SOIC8"))
    )
    (comp (ref "IC10")
      (value "MC33272ADR2G")
      (footprint "eagle-import:SOIC127P600X173-8N")
      (libsource (lib "eagle-import") (part "TL072SOIC8"))
    )
    (comp (ref "IC11")
      (value "LTC2050HVCS8#PBF")
      (footprint "eagle-import:SOIC127P600X173-8N")
      (libsource (lib "eagle-import") (part "OP27GSZSO8"))
    )
    (comp (ref "KK3")
      (value "SK96/84")
      (footprint "eagle-import:SK96_84")
      (libsource (lib "eagle-import") (part "SK96/84"))
    )
    (comp (ref "Q3")
      (value "D45H11")
      (footprint "eagle-import:TO220BV")
      (libsource (lib "eagle-import") (part "D45H11-VERT"))
    )
    (comp (ref "Q4")
      (value "D45H11")
      (footprint "eagle-import:TO220BV")
      (libsource (lib "eagle-import") (part "D45H11-VERT"))
    )
    (comp (ref "Q5")
      (value "BC856C")
      (footprint "eagle-import:SOT23-BEC")
      (libsource (lib "eagle-import") (part "-PNP-SOT23-BECBC857C"))
    )
    (comp (ref "Q6")
      (value "MMBT5401")
      (footprint "eagle-import:SOT23-BEC")
      (libsource (lib "eagle-import") (part "-PNP-SOT23-BECBC857B"))
    )
    (comp (ref "Q7")
      (value "STF10P6F6")
      (footprint "eagle-import:TO220BV")
      (libsource (lib "eagle-import") (part "P-MOSFET-VERT"))
    )
    (comp (ref "Q8")
      (value "BCP56-16.115")
      (footprint "eagle-import:SOT230P700X180-4N")
      (libsource (lib "eagle-import") (part "BCP56"))
    )
    (comp (ref "Q9")
      (value "NZT605")
      (footprint "eagle-import:SOT230P700X180-4N")
      (libsource (lib "eagle-import") (part "NZT605"))
    )
    (comp (ref "Q9B")
      (value "BDX33C")
      (footprint "eagle-import:TO220BV")
      (libsource (lib "eagle-import") (part "BDX33C"))
    )
    (comp (ref "Q10")
      (value "BSS205NH6327XTSA1")
      (footprint "eagle-import:SOT103P240X110-3N")
      (fields
        (field (name "MPN") "2N7002-7-F")
        (field (name "MPN_1") "2N7002-7-F")
        (field (name "OC_FARNELL") "1713823")
        (field (name "OC_NEWARK") "25R5679")
        (field (name "PACKAGE") "SOT-23-3")
        (field (name "SUPPLIER") "DIODES INC.")
      )
      (libsource (lib "eagle-import") (part "2N7002"))
    )
    (comp (ref "Q11")
      (value "PSMN0R9-25YLC")
      (footprint "eagle-import:SOT669")
      (libsource (lib "eagle-import") (part "N-MOSFETLFPAK"))
    )
    (comp (ref "Q12")
      (value "PSMN0R9-25YLC")
      (footprint "eagle-import:SOT669")
      (libsource (lib "eagle-import") (part "N-MOSFETLFPAK"))
    )
    (comp (ref "R27")
      (value "0R1/2-3W")
      (footprint "eagle-import:R2512")
      (libsource (lib "eagle-import") (part "R-EU_R2512"))
    )
    (comp (ref "R28")
      (value "2R2/2W")
      (footprint "eagle-import:R2512")
      (libsource (lib "eagle-import") (part "R-EU_R2512"))
    )
    (comp (ref "R29")
      (value "0R1/2-3W")
      (footprint "eagle-import:R2512")
      (libsource (lib "eagle-import") (part "R-EU_R2512"))
    )
    (comp (ref "R30")
      (value "2K2")
      (footprint "eagle-import:R0805")
      (libsource (lib "eagle-import") (part "R-EU_R0805"))
    )
    (comp (ref "R31")
      (value "10K")
      (footprint "eagle-import:R0805")
      (libsource (lib "eagle-import") (part "R-EU_R0805"))
    )
    (comp (ref "R32")
      (value "10R")
      (footprint "eagle-import:R1206")
      (libsource (lib "eagle-import") (part "R-EU_R1206"))
    )
    (comp (ref "R33")
      (value "10R")
      (footprint "eagle-import:R1206")
      (libsource (lib "eagle-import") (part "R-EU_R1206"))
    )
    (comp (ref "R34")
      (value "2K2")
      (footprint "eagle-import:R0805")
      (libsource (lib "eagle-import") (part "R-EU_R0805"))
    )
    (comp (ref "R35")
      (value "470R")
      (footprint "eagle-import:R0805")
      (libsource (lib "eagle-import") (part "R-EU_R0805"))
    )
    (comp (ref "R36")
      (value "220R")
      (footprint "eagle-import:R0805")
      (libsource (lib "eagle-import") (part "R-EU_R0805"))
    )
    (comp (ref "R37")
      (value "10R")
      (footprint "eagle-import:R1206")
      (libsource (lib "eagle-import") (part "R-EU_R1206"))
    )
    (comp (ref "R38")
      (value "1R")
      (footprint "eagle-import:R0805")
      (libsource (lib "eagle-import") (part "R-EU_R0805"))
    )
    (comp (ref "R39")
      (value "1K")
      (footprint "eagle-import:R0805")
      (libsource (lib "eagle-import") (part "R-EU_R0805"))
    )
    (comp (ref "R40")
      (value "7K5 0.1%")
      (footprint "eagle-import:R0805")
      (libsource (lib "eagle-import") (part "R-EU_R0805"))
    )
    (comp (ref "R41")
      (value "10K")
      (footprint "eagle-import:R0805")
      (libsource (lib "eagle-import") (part "R-EU_R0805"))
    )
    (comp (ref "R42")
      (value "220R")
      (footprint "eagle-import:R0805")
      (libsource (lib "eagle-import") (part "R-EU_R0805"))
    )
    (comp (ref "R43")
      (value "2K2")
      (footprint "eagle-import:R0805")
      (libsource (lib "eagle-import") (part "R-EU_R0805"))
    )
    (comp (ref "R44")
      (value "100K 0.1%")
      (footprint "eagle-import:R0805")
      (libsource (lib "eagle-import") (part "R-EU_R0805"))
    )
    (comp (ref "R45")
      (value "24K 0.1%")
      (footprint "eagle-import:R0805")
      (libsource (lib "eagle-import") (part "R-EU_R0805"))
    )
    (comp (ref "R46")
      (value "220R")
      (footprint "eagle-import:R0805")
      (libsource (lib "eagle-import") (part "R-EU_R0805"))
    )
    (comp (ref "R47")
      (value "10K")
      (footprint "eagle-import:R0805")
      (libsource (lib "eagle-import") (part "R-EU_R0805"))
    )
    (comp (ref "R48")
      (value "10K")
      (footprint "eagle-import:R0805")
      (libsource (lib "eagle-import") (part "R-EU_R0805"))
    )
    (comp (ref "R49")
      (value "7K5 0.1%")
      (footprint "eagle-import:R0805")
      (libsource (lib "eagle-import") (part "R-EU_R0805"))
    )
    (comp (ref "R50")
      (value "100K 0.1%")
      (footprint "eagle-import:R0805")
      (libsource (lib "eagle-import") (part "R-EU_R0805"))
    )
    (comp (ref "R51")
      (value "24K 0.1%")
      (footprint "eagle-import:R0805")
      (libsource (lib "eagle-import") (part "R-EU_R0805"))
    )
    (comp (ref "R52")
      (value "15R")
      (footprint "eagle-import:R1206")
      (libsource (lib "eagle-import") (part "R-EU_R1206"))
    )
    (comp (ref "R53")
      (value "0R")
      (footprint "eagle-import:R0805")
      (libsource (lib "eagle-import") (part "R-EU_R0805"))
    )
    (comp (ref "R54")
      (value "10K")
      (footprint "eagle-import:R0805")
      (libsource (lib "eagle-import") (part "R-EU_R0805"))
    )
    (comp (ref "R55")
      (value "220R")
      (footprint "eagle-import:R0805")
      (libsource (lib "eagle-import") (part "R-EU_R0805"))
    )
    (comp (ref "R56")
      (value "100K")
      (footprint "eagle-import:R0805")
      (libsource (lib "eagle-import") (part "R-EU_R0805"))
    )
    (comp (ref "R57")
      (value "39K 0.1%")
      (footprint "eagle-import:R0805")
      (libsource (lib "eagle-import") (part "R-EU_R0805"))
    )
    (comp (ref "R58")
      (value "820R 0.1%")
      (footprint "eagle-import:R0805")
      (libsource (lib "eagle-import") (part "R-EU_R0805"))
    )
    (comp (ref "R59")
      (value "47K")
      (footprint "eagle-import:R0805")
      (libsource (lib "eagle-import") (part "R-EU_R0805"))
    )
    (comp (ref "R60")
      (value "2K2")
      (footprint "eagle-import:R0805")
      (libsource (lib "eagle-import") (part "R-EU_R0805"))
    )
    (comp (ref "R61")
      (value "0R75")
      (footprint "eagle-import:R1206")
      (libsource (lib "eagle-import") (part "R-EU_R1206"))
    )
    (comp (ref "R62")
      (value "10K")
      (footprint "eagle-import:R0805")
      (libsource (lib "eagle-import") (part "R-EU_R0805"))
    )
    (comp (ref "R63")
      (value "10K")
      (footprint "eagle-import:R0805")
      (libsource (lib "eagle-import") (part "R-EU_R0805"))
    )
    (comp (ref "R64")
      (value "39K 0.1%")
      (footprint "eagle-import:R0805")
      (libsource (lib "eagle-import") (part "R-EU_R0805"))
    )
    (comp (ref "R65")
      (value "47K")
      (footprint "eagle-import:R0805")
      (libsource (lib "eagle-import") (part "R-EU_R0805"))
    )
    (comp (ref "R66")
      (value "10K")
      (footprint "eagle-import:R0805")
      (libsource (lib "eagle-import") (part "R-EU_R0805"))
    )
    (comp (ref "R67")
      (value "0R010 (low TCR)")
      (footprint "eagle-import:R_2512-4WIRE")
      (libsource (lib "eagle-import") (part "R-EU_4WIRE2512"))
    )
    (comp (ref "R68")
      (value "820R 0.1%")
      (footprint "eagle-import:R0805")
      (libsource (lib "eagle-import") (part "R-EU_R0805"))
    )
    (comp (ref "C86")
      (value "10n")
      (footprint "eagle-import:C0805")
      (libsource (lib "eagle-import") (part "C-EUC0805"))
    )
    (comp (ref "C87")
      (value "2n2")
      (footprint "eagle-import:C0805")
      (libsource (lib "eagle-import") (part "C-EUC0805"))
    )
    (comp (ref "C88")
      (value "470n")
      (footprint "eagle-import:C1206")
      (libsource (lib "eagle-import") (part "C-EUC1206"))
    )
    (comp (ref "C89")
      (value "HHXC630ARA220MHA0G")
      (footprint "eagle-import:CAPAE830X1050N")
      (libsource (lib "eagle-import") (part "ECAPSMD8.3MM/HA0"))
    )
    (comp (ref "C90")
      (value "10n/200V")
      (footprint "eagle-import:C1206")
      (libsource (lib "eagle-import") (part "C-EUC1206"))
    )
    (comp (ref "C91")
      (value "N.C.")
      (footprint "eagle-import:ECAP2_5")
      (libsource (lib "eagle-import") (part "ECAP2G/5"))
    )
    (comp (ref "C92")
      (value "N.C.")
      (footprint "eagle-import:C0805")
      (libsource (lib "eagle-import") (part "C-EUC0805"))
    )
    (comp (ref "C93")
      (value "N.C.")
      (footprint "eagle-import:C0805")
      (libsource (lib "eagle-import") (part "C-EUC0805"))
    )
    (comp (ref "C94")
      (value "10n/200V")
      (footprint "eagle-import:C1206")
      (libsource (lib "eagle-import") (part "C-EUC1206"))
    )
    (comp (ref "C95")
      (value "10n")
      (footprint "eagle-import:C0805")
      (libsource (lib "eagle-import") (part "C-EUC0805"))
    )
    (comp (ref "D20")
      (value "SK10100D1-DIO")
      (footprint "eagle-import:TO252-L")
      (libsource (lib "eagle-import") (part "SCHOTTKY-DUAL_A_L"))
    )
    (comp (ref "D21")
      (value "BAS316")
      (footprint "eagle-import:SOD323-R")
      (libsource (lib "eagle-import") (part "DIODESOD323R"))
    )
    (comp (ref "F1")
      (value "ZH32")
      (footprint "eagle-import:ZH32")
      (libsource (lib "eagle-import") (part "ZH32"))
    )
    (comp (ref "F2")
      (value "ZH32")
      (footprint "eagle-import:ZH32")
      (libsource (lib "eagle-import") (part "ZH32"))
    )
    (comp (ref "J2")
      (value "FCR7350R")
      (footprint "eagle-import:S16N-PC")
      (libsource (lib "eagle-import") (part "BINDING_POSTCLIFF"))
    )
    (comp (ref "J3")
      (value "FCR7350B")
      (footprint "eagle-import:S16N-PC")
      (libsource (lib "eagle-import") (part "BINDING_POSTCLIFF"))
    )
    (comp (ref "JP4")
      (value "JP2-CUT")
      (footprint "eagle-import:JP2-CUT")
      (libsource (lib "eagle-import") (part "JP2-CUT"))
    )
    (comp (ref "JP5")
      (value "JP2-CUT")
      (footprint "eagle-import:JP2-CUT")
      (libsource (lib "eagle-import") (part "JP2-CUT"))
    )
    (comp (ref "K1")
      (value "G6K-2F-5DC")
      (footprint "eagle-import:G6K-2F")
      (fields
        (field (name "MF") "OMRON COMPONENTS USA")
        (field (name "MPN") "G6K-2F DC24")
        (field (name "MF_1") "OMRON COMPONENTS USA")
        (field (name "MPN_1") "G6K-2F DC24")
        (field (name "OC_FARNELL") "1690427")
        (field (name "OC_NEWARK") "36K7467")
      )
      (libsource (lib "eagle-import") (part "G6K-2F"))
    )
    (comp (ref "Q19")
      (value "MMBT5551")
      (footprint "eagle-import:SOT23-BEC")
      (libsource (lib "eagle-import") (part "-NPN-SOT23-BECMMBT5551LT1"))
    )
    (comp (ref "Q20")
      (value "MMBT5401")
      (footprint "eagle-import:SOT23-BEC")
      (libsource (lib "eagle-import") (part "-PNP-SOT23-BECBC857B"))
    )
    (comp (ref "Q21")
      (value "MMBT5551")
      (footprint "eagle-import:SOT23-BEC")
      (libsource (lib "eagle-import") (part "-NPN-SOT23-BECMMBT5551LT1"))
    )
    (comp (ref "Q22")
      (value "MMBT5551")
      (footprint "eagle-import:SOT23-BEC")
      (libsource (lib "eagle-import") (part "-NPN-SOT23-BECMMBT5551LT1"))
    )
    (comp (ref "Q23")
      (value "2N7002")
      (footprint "eagle-import:SOT103P240X110-3N")
      (fields
        (field (name "MPN") "2N7002-7-F")
        (field (name "MPN_1") "2N7002-7-F")
        (field (name "OC_FARNELL") "1713823")
        (field (name "OC_NEWARK") "25R5679")
        (field (name "PACKAGE") "SOT-23-3")
        (field (name "SUPPLIER") "DIODES INC.")
      )
      (libsource (lib "eagle-import") (part "2N7002"))
    )
    (comp (ref "R102")
      (value "330R")
      (footprint "eagle-import:R0805")
      (libsource (lib "eagle-import") (part "R-EU_R0805"))
    )
    (comp (ref "R103")
      (value "47K")
      (footprint "eagle-import:R0805")
      (libsource (lib "eagle-import") (part "R-EU_R0805"))
    )
    (comp (ref "R104")
      (value "47K")
      (footprint "eagle-import:R0805")
      (libsource (lib "eagle-import") (part "R-EU_R0805"))
    )
    (comp (ref "R105")
      (value "750R")
      (footprint "eagle-import:R0805")
      (libsource (lib "eagle-import") (part "R-EU_R0805"))
    )
    (comp (ref "R106")
      (value "1K")
      (footprint "eagle-import:R0805")
      (libsource (lib "eagle-import") (part "R-EU_R0805"))
    )
    (comp (ref "R107")
      (value "2K2")
      (footprint "eagle-import:R0805")
      (libsource (lib "eagle-import") (part "R-EU_R0805"))
    )
    (comp (ref "R108")
      (value "10K")
      (footprint "eagle-import:R0805")
      (libsource (lib "eagle-import") (part "R-EU_R0805"))
    )
    (comp (ref "R109")
      (value "10K")
      (footprint "eagle-import:R0805")
      (libsource (lib "eagle-import") (part "R-EU_R0805"))
    )
    (comp (ref "R110")
      (value "1R")
      (footprint "eagle-import:R0805")
      (libsource (lib "eagle-import") (part "R-EU_R0805"))
    )
    (comp (ref "R111")
      (value "750R")
      (footprint "eagle-import:R0805")
      (libsource (lib "eagle-import") (part "R-EU_R0805"))
    )
    (comp (ref "R112")
      (value "47K")
      (footprint "eagle-import:R0805")
      (libsource (lib "eagle-import") (part "R-EU_R0805"))
    )
    (comp (ref "R113")
      (value "330R")
      (footprint "eagle-import:R0805")
      (libsource (lib "eagle-import") (part "R-EU_R0805"))
    )
    (comp (ref "R114")
      (value "470R")
      (footprint "eagle-import:R0805")
      (libsource (lib "eagle-import") (part "R-EU_R0805"))
    )
    (comp (ref "R115")
      (value "100K")
      (footprint "eagle-import:R0805")
      (libsource (lib "eagle-import") (part "R-EU_R0805"))
    )
    (comp (ref "X4")
      (value "DS1024-2*10R0")
      (footprint "eagle-import:SSW-110-02-T-D-RA")
      (libsource (lib "eagle-import") (part "SSW-110-02-T-D-RA"))
    )
    (comp (ref "C80")
      (value "100n")
      (footprint "eagle-import:C0603")
      (libsource (lib "eagle-import") (part "C-EUC0603"))
    )
    (comp (ref "C81")
      (value "N.C.")
      (footprint "eagle-import:C0805")
      (libsource (lib "eagle-import") (part "C-EUC0805"))
    )
    (comp (ref "C82")
      (value "100n")
      (footprint "eagle-import:C0603")
      (libsource (lib "eagle-import") (part "C-EUC0603"))
    )
    (comp (ref "C83")
      (value "1n")
      (footprint "eagle-import:C0805")
      (libsource (lib "eagle-import") (part "C-EUC0805"))
    )
    (comp (ref "C84")
      (value "100n")
      (footprint "eagle-import:C0603")
      (libsource (lib "eagle-import") (part "C-EUC0603"))
    )
    (comp (ref "C85")
      (value "1n")
      (footprint "eagle-import:C0805")
      (libsource (lib "eagle-import") (part "C-EUC0805"))
    )
    (comp (ref "D18")
      (value "BAS316")
      (footprint "eagle-import:SOD323-R")
      (libsource (lib "eagle-import") (part "DIODESOD323R"))
    )
    (comp (ref "D19")
      (value "BAS316")
      (footprint "eagle-import:SOD323-R")
      (libsource (lib "eagle-import") (part "DIODESOD323R"))
    )
    (comp (ref "IC19")
      (value "LM339D")
      (footprint "eagle-import:SOIC127P600X175-14N")
      (libsource (lib "eagle-import") (part "LM339SO14"))
    )
    (comp (ref "IC20")
      (value "MAX9141ESA")
      (footprint "eagle-import:SOIC127P600X173-8N")
      (libsource (lib "eagle-import") (part "MAX9141ESA"))
    )
    (comp (ref "JP2")
      (value "JP3-CUT-ROTATED")
      (footprint "eagle-import:JP3-CUT2")
      (libsource (lib "eagle-import") (part "JP3-CUT-ROTATED"))
    )
    (comp (ref "JP3")
      (value "JP3-CUT")
      (footprint "eagle-import:JP3-CUT")
      (libsource (lib "eagle-import") (part "JP3-CUT"))
    )
    (comp (ref "LED3")
      (value "WP934MD/LYLID")
      (footprint "eagle-import:WP934MD")
      (libsource (lib "eagle-import") (part "WP934MD/LYLID"))
    )
    (comp (ref "Q14")
      (value "BTA26-600")
      (footprint "eagle-import:TOP3_TRIAC_NOHOLE")
      (libsource (lib "eagle-import") (part "BTA41-2"))
    )
    (comp (ref "Q15")
      (value "FMMT493TA")
      (footprint "eagle-import:SOT23-BEC")
      (libsource (lib "eagle-import") (part "-NPN-SOT23-BECMMBT5551LT1"))
    )
    (comp (ref "Q16")
      (value "2N7002")
      (footprint "eagle-import:SOT103P240X110-3N")
      (fields (field (name "MPN") "2N7002-7-F"))
      (libsource (lib "eagle-import") (part "2N7002"))
    )
    (comp (ref "Q17")
      (value "2N7002")
      (footprint "eagle-import:SOT103P240X110-3N")
      (fields (field (name "MPN") "2N7002-7-F"))
      (libsource (lib "eagle-import") (part "2N7002"))
    )
    (comp (ref "Q18")
      (value "2N7002")
      (footprint "eagle-import:SOT103P240X110-3N")
      (fields
        (field (name "MPN") "2N7002-7-F")
        (field (name "MPN_1") "2N7002-7-F")
        (field (name "OC_FARNELL") "1713823")
        (field (name "OC_NEWARK") "25R5679")
        (field (name "PACKAGE") "SOT-23-3")
        (field (name "SUPPLIER") "DIODES INC.")
      )
      (libsource (lib "eagle-import") (part "2N7002"))
    )
    (comp (ref "R81")
      (value "10K")
      (footprint "eagle-import:R0805")
      (libsource (lib "eagle-import") (part "R-EU_R0805"))
    )
    (comp (ref "R82")
      (value "750R")
      (footprint "eagle-import:R0805")
      (libsource (lib "eagle-import") (part "R-EU_R0805"))
    )
    (comp (ref "R83")
      (value "470R")
      (footprint "eagle-import:R0805")
      (libsource (lib "eagle-import") (part "R-EU_R0805"))
    )
    (comp (ref "R84")
      (value "5K1")
      (footprint "eagle-import:R0805")
      (libsource (lib "eagle-import") (part "R-EU_R0805"))
    )
    (comp (ref "R85")
      (value "47K")
      (footprint "eagle-import:R0805")
      (libsource (lib "eagle-import") (part "R-EU_R0805"))
    )
    (comp (ref "R86")
      (value "5K6")
      (footprint "eagle-import:R0805")
      (libsource (lib "eagle-import") (part "R-EU_R0805"))
    )
    (comp (ref "R87")
      (value "10K")
      (footprint "eagle-import:R0805")
      (libsource (lib "eagle-import") (part "R-EU_R0805"))
    )
    (comp (ref "R88")
      (value "330R")
      (footprint "eagle-import:R0805")
      (libsource (lib "eagle-import") (part "R-EU_R0805"))
    )
    (comp (ref "R89")
      (value "1K")
      (footprint "eagle-import:R0805")
      (libsource (lib "eagle-import") (part "R-EU_R0805"))
    )
    (comp (ref "R90")
      (value "AC01000001007JA100")
      (footprint "eagle-import:0411_15")
      (libsource (lib "eagle-import") (part "R-EU_0411/15"))
    )
    (comp (ref "R91")
      (value "2K2")
      (footprint "eagle-import:R0805")
      (libsource (lib "eagle-import") (part "R-EU_R0805"))
    )
    (comp (ref "R92")
      (value "330R")
      (footprint "eagle-import:R0805")
      (libsource (lib "eagle-import") (part "R-EU_R0805"))
    )
    (comp (ref "R93")
      (value "10K")
      (footprint "eagle-import:R0805")
      (libsource (lib "eagle-import") (part "R-EU_R0805"))
    )
    (comp (ref "R94")
      (value "100K")
      (footprint "eagle-import:R0805")
      (libsource (lib "eagle-import") (part "R-EU_R0805"))
    )
    (comp (ref "R95")
      (value "6R2")
      (footprint "eagle-import:R0805")
      (libsource (lib "eagle-import") (part "R-EU_R0805"))
    )
    (comp (ref "R96")
      (value "10K")
      (footprint "eagle-import:R0805")
      (libsource (lib "eagle-import") (part "R-EU_R0805"))
    )
    (comp (ref "R97")
      (value "5K1")
      (footprint "eagle-import:R0805")
      (libsource (lib "eagle-import") (part "R-EU_R0805"))
    )
    (comp (ref "R98")
      (value "10K")
      (footprint "eagle-import:R0805")
      (libsource (lib "eagle-import") (part "R-EU_R0805"))
    )
    (comp (ref "R99")
      (value "5K6")
      (footprint "eagle-import:R0805")
      (libsource (lib "eagle-import") (part "R-EU_R0805"))
    )
    (comp (ref "R100")
      (value "10K")
      (footprint "eagle-import:R0805")
      (libsource (lib "eagle-import") (part "R-EU_R0805"))
    )
    (comp (ref "R101")
      (value "N.C.")
      (footprint "eagle-import:R0805")
      (libsource (lib "eagle-import") (part "R-EU_R0805"))
    )
    (comp (ref "C20")
      (value "4u7")
      (footprint "eagle-import:C1206")
      (libsource (lib "eagle-import") (part "C-EUC1206"))
    )
    (comp (ref "C21")
      (value "4u7")
      (footprint "eagle-import:C1206")
      (libsource (lib "eagle-import") (part "C-EUC1206"))
    )
    (comp (ref "C22")
      (value "2u2")
      (footprint "eagle-import:C1206")
      (libsource (lib "eagle-import") (part "C-EUC1206"))
    )
    (comp (ref "C23")
      (value "2u2")
      (footprint "eagle-import:C1206")
      (libsource (lib "eagle-import") (part "C-EUC1206"))
    )
    (comp (ref "C24")
      (value "100n")
      (footprint "eagle-import:C0603")
      (libsource (lib "eagle-import") (part "C-EUC0603"))
    )
    (comp (ref "C25")
      (value "330p")
      (footprint "eagle-import:C0805")
      (libsource (lib "eagle-import") (part "C-EUC0805"))
    )
    (comp (ref "C26")
      (value "22u")
      (footprint "eagle-import:C1206")
      (libsource (lib "eagle-import") (part "C-EUC1206"))
    )
    (comp (ref "C27")
      (value "22u")
      (footprint "eagle-import:C1206")
      (libsource (lib "eagle-import") (part "C-EUC1206"))
    )
    (comp (ref "C28")
      (value "4u7")
      (footprint "eagle-import:C1206")
      (libsource (lib "eagle-import") (part "C-EUC1206"))
    )
    (comp (ref "C29")
      (value "100n")
      (footprint "eagle-import:C0603")
      (libsource (lib "eagle-import") (part "C-EUC0603"))
    )
    (comp (ref "C30")
      (value "18p")
      (footprint "eagle-import:C0603")
      (libsource (lib "eagle-import") (part "C-EUC0603"))
    )
    (comp (ref "C31")
      (value "100n")
      (footprint "eagle-import:C0603")
      (libsource (lib "eagle-import") (part "C-EUC0603"))
    )
    (comp (ref "C32")
      (value "100n")
      (footprint "eagle-import:C0603")
      (libsource (lib "eagle-import") (part "C-EUC0603"))
    )
    (comp (ref "C33")
      (value "100n")
      (footprint "eagle-import:C0603")
      (libsource (lib "eagle-import") (part "C-EUC0603"))
    )
    (comp (ref "C34")
      (value "10n")
      (footprint "eagle-import:C0805")
      (libsource (lib "eagle-import") (part "C-EUC0805"))
    )
    (comp (ref "C35")
      (value "100n")
      (footprint "eagle-import:C0603")
      (libsource (lib "eagle-import") (part "C-EUC0603"))
    )
    (comp (ref "C36")
      (value "100n")
      (footprint "eagle-import:C0603")
      (libsource (lib "eagle-import") (part "C-EUC0603"))
    )
    (comp (ref "C37")
      (value "100n")
      (footprint "eagle-import:C0603")
      (libsource (lib "eagle-import") (part "C-EUC0603"))
    )
    (comp (ref "C38")
      (value "100n")
      (footprint "eagle-import:C0603")
      (libsource (lib "eagle-import") (part "C-EUC0603"))
    )
    (comp (ref "C39")
      (value "100n")
      (footprint "eagle-import:C0603")
      (libsource (lib "eagle-import") (part "C-EUC0603"))
    )
    (comp (ref "D4")
      (value "SKL16")
      (footprint "eagle-import:SOD123")
      (libsource (lib "eagle-import") (part "SCHOTTKYSOD123"))
    )
    (comp (ref "D5")
      (value "SKL16")
      (footprint "eagle-import:SOD123")
      (libsource (lib "eagle-import") (part "SCHOTTKYSOD123"))
    )
    (comp (ref "D6")
      (value "SKL14")
      (footprint "eagle-import:SOD123")
      (libsource (lib "eagle-import") (part "SCHOTTKYSOD123"))
    )
    (comp (ref "D7")
      (value "SKL14")
      (footprint "eagle-import:SOD123")
      (libsource (lib "eagle-import") (part "SCHOTTKYSOD123"))
    )
    (comp (ref "FB1")
      (value "60R@100MHz")
      (footprint "eagle-import:BEAD0603")
      (libsource (lib "eagle-import") (part "FERRITE_BEAD0603"))
    )
    (comp (ref "FB2")
      (value "60R@100MHz")
      (footprint "eagle-import:BEAD0603")
      (libsource (lib "eagle-import") (part "FERRITE_BEAD0603"))
    )
    (comp (ref "FB3")
      (value "60R@100MHz")
      (footprint "eagle-import:BEAD0603")
      (libsource (lib "eagle-import") (part "FERRITE_BEAD0603"))
    )
    (comp (ref "FM1")
      (value "FIDUCIAL_2")
      (footprint "eagle-import:FIDUCIAL_DUAL")
      (libsource (lib "eagle-import") (part "FIDUCIAL_2"))
    )
    (comp (ref "FM2")
      (value "FIDUCIAL_2")
      (footprint "eagle-import:FIDUCIAL_DUAL")
      (libsource (lib "eagle-import") (part "FIDUCIAL_2"))
    )
    (comp (ref "IC2")
      (value "TPS54060DGQ")
      (footprint "eagle-import:SOP50P490X110-11N")
      (fields (field (name "MPN") "TPS54060ADGQ"))
      (libsource (lib "eagle-import") (part "TPS54060DGQ"))
    )
    (comp (ref "IC3")
      (value "SI8641BB-B-IS1")
      (footprint "eagle-import:SOIC-16")
      (libsource (lib "eagle-import") (part "SI8641NSOIC-16"))
    )
    (comp (ref "IC4")
      (value "SN74LVC1G139DCUR")
      (footprint "eagle-import:DCU8")
      (libsource (lib "eagle-import") (part "SN74LVC1G139-VSSOP"))
    )
    (comp (ref "IC5")
      (value "MC78L05")
      (footprint "eagle-import:SOIC127P600X173-8N")
      (libsource (lib "eagle-import") (part "MC78LXXSOIC8"))
    )
    (comp (ref "IC6")
      (value "MC79L05")
      (footprint "eagle-import:SOIC127P600X173-8N")
      (libsource (lib "eagle-import") (part "MC79LXXSOIC"))
    )
    (comp (ref "IC7")
      (value "SI8641BB-B-IS1")
      (footprint "eagle-import:SOIC-16")
      (libsource (lib "eagle-import") (part "SI8641NSOIC-16"))
    )
    (comp (ref "IC8")
      (value "M24C32-WMN6P")
      (footprint "eagle-import:SOIC127P600X173-8N")
      (libsource (lib "eagle-import") (part "AT24CXXSOIC8"))
    )
    (comp (ref "KK1")
      (value "PCB-MB-01")
      (footprint "eagle-import:PCB-MB")
      (libsource (lib "eagle-import") (part "PCB-MB"))
    )
    (comp (ref "KK2")
      (value "PCB-MB-01")
      (footprint "eagle-import:PCB-MB")
      (libsource (lib "eagle-import") (part "PCB-MB"))
    )
    (comp (ref "R14")
      (value "10R")
      (footprint "eagle-import:R1206")
      (libsource (lib "eagle-import") (part "R-EU_R1206"))
    )
    (comp (ref "R15")
      (value "47K")
      (footprint "eagle-import:R0805")
      (libsource (lib "eagle-import") (part "R-EU_R0805"))
    )
    (comp (ref "R16")
      (value "10R")
      (footprint "eagle-import:R1206")
      (libsource (lib "eagle-import") (part "R-EU_R1206"))
    )
    (comp (ref "R17")
      (value "10R")
      (footprint "eagle-import:R1206")
      (libsource (lib "eagle-import") (part "R-EU_R1206"))
    )
    (comp (ref "R18")
      (value "2K2")
      (footprint "eagle-import:R0805")
      (libsource (lib "eagle-import") (part "R-EU_R0805"))
    )
    (comp (ref "R19")
      (value "10K")
      (footprint "eagle-import:R0805")
      (libsource (lib "eagle-import") (part "R-EU_R0805"))
    )
    (comp (ref "R20")
      (value "100K")
      (footprint "eagle-import:R0805")
      (libsource (lib "eagle-import") (part "R-EU_R0805"))
    )
    (comp (ref "R21")
      (value "330K")
      (footprint "eagle-import:R0805")
      (libsource (lib "eagle-import") (part "R-EU_R0805"))
    )
    (comp (ref "R22")
      (value "86K6")
      (footprint "eagle-import:R0805")
      (libsource (lib "eagle-import") (part "R-EU_R0805"))
    )
    (comp (ref "R23")
      (value "10K")
      (footprint "eagle-import:R0805")
      (libsource (lib "eagle-import") (part "R-EU_R0805"))
    )
    (comp (ref "R24")
      (value "10K")
      (footprint "eagle-import:R0805")
      (libsource (lib "eagle-import") (part "R-EU_R0805"))
    )
    (comp (ref "R25")
      (value "10K")
      (footprint "eagle-import:R0805")
      (libsource (lib "eagle-import") (part "R-EU_R0805"))
    )
    (comp (ref "R26")
      (value "10K")
      (footprint "eagle-import:R0805")
      (libsource (lib "eagle-import") (part "R-EU_R0805"))
    )
    (comp (ref "RN1")
      (value "DR1206-33R-4/8")
      (footprint "eagle-import:CAY16")
      (libsource (lib "eagle-import") (part "R_ARRAY4"))
    )
    (comp (ref "RN2")
      (value "DR1206-33R-4/8")
      (footprint "eagle-import:CAY16")
      (libsource (lib "eagle-import") (part "R_ARRAY4"))
    )
    (comp (ref "TR1")
      (value "SRF0703-821M")
      (footprint "eagle-import:SRF0703")
      (libsource (lib "eagle-import") (part "BOURNS_SRF0703INV"))
    )
    (comp (ref "X2")
      (value "77317-104-28LF")
      (footprint "eagle-import:77317-104-28LF")
      (libsource (lib "eagle-import") (part "77317-104-28LF"))
    )
  )
  (nets
    (net (code "1") (name "+3V3") (class "Default")
      (node (ref "C31") (pin "1") (pinfunction "1_1") (pintype "passive"))
      (node (ref "C36") (pin "1") (pinfunction "1_1") (pintype "passive"))
      (node (ref "C39") (pin "2") (pinfunction "2_2") (pintype "passive"))
      (node (ref "IC3") (pin "1") (pinfunction "VDD1_1") (pintype "passive"))
      (node (ref "IC3") (pin "7") (pinfunction "EN1_7") (pintype "input"))
      (node (ref "IC7") (pin "1") (pinfunction "VDD1_1") (pintype "passive"))
      (node (ref "IC7") (pin "7") (pinfunction "EN1_7") (pintype "input"))
      (node (ref "IC8") (pin "8") (pinfunction "VCC_8") (pintype "power_in"))
      (node (ref "R24") (pin "1") (pinfunction "1_1") (pintype "passive"))
      (node (ref "R25") (pin "1") (pinfunction "1_1") (pintype "passive"))
      (node (ref "R26") (pin "1") (pinfunction "1_1") (pintype "passive"))
      (node (ref "X2") (pin "1") (pinfunction "1_1") (pintype "passive"))
    )
    (net (code "2") (name "+5V") (class "Default")
      (node (ref "C32") (pin "2") (pinfunction "2_2") (pintype "passive"))
      (node (ref "C33") (pin "1") (pinfunction "1_1") (pintype "passive"))
      (node (ref "C37") (pin "2") (pinfunction "2_2") (pintype "passive"))
      (node (ref "C60") (pin "1") (pinfunction "1_1") (pintype "passive"))
      (node (ref "C61") (pin "2") (pinfunction "2_2") (pintype "passive"))
      (node (ref "C63") (pin "1") (pinfunction "1_1") (pintype "passive"))
      (node (ref "C75") (pin "2") (pinfunction "2_2") (pintype "passive"))
      (node (ref "C76") (pin "2") (pinfunction "2_2") (pintype "passive"))
      (node (ref "D21") (pin "C") (pinfunction "C_C") (pintype "passive"))
      (node (ref "FB2") (pin "P$2") (pinfunction "2_P$2") (pintype "passive"))
      (node (ref "IC12") (pin "7") (pinfunction "~{PRE}_7") (pintype "input"))
      (node (ref "IC12") (pin "8") (pinfunction "VDD_8") (pintype "power_in"))
      (node (ref "IC13") (pin "9") (pinfunction "VDD_9") (pintype "power_in"))
      (node (ref "IC14") (pin "5") (pinfunction "VDD_5") (pintype "passive"))
      (node (ref "IC18") (pin "13") (pinfunction "DVDD_13") (pintype "power_in"))
      (node (ref "IC3") (pin "10") (pinfunction "EN2_10") (pintype "input"))
      (node (ref "IC3") (pin "16") (pinfunction "VDD2_16") (pintype "passive"))
      (node (ref "IC4") (pin "8") (pinfunction "VCC_8") (pintype "passive"))
      (node (ref "IC7") (pin "10") (pinfunction "EN2_10") (pintype "input"))
      (node (ref "IC7") (pin "16") (pinfunction "VDD2_16") (pintype "passive"))
      (node (ref "K1") (pin "1") (pinfunction "+_1") (pintype "passive"))
      (node (ref "LED1") (pin "BA") (pinfunction "A_BA") (pintype "passive"))
      (node (ref "LED3") (pin "BA") (pinfunction "A_BA") (pintype "passive"))
      (node (ref "LED3") (pin "TA") (pinfunction "A_TA") (pintype "passive"))
      (node (ref "Q13") (pin "2") (pinfunction "S_2") (pintype "passive"))
      (node (ref "R108") (pin "2") (pinfunction "2_2") (pintype "passive"))
      (node (ref "R19") (pin "1") (pinfunction "1_1") (pintype "passive"))
      (node (ref "R69") (pin "1") (pinfunction "1_1") (pintype "passive"))
      (node (ref "R70") (pin "1") (pinfunction "1_1") (pintype "passive"))
      (node (ref "R84") (pin "2") (pinfunction "2_2") (pintype "passive"))
      (node (ref "R97") (pin "2") (pinfunction "2_2") (pintype "passive"))
    )
    (net (code "3") (name "+VAUX") (class "Default")
      (node (ref "X2") (pin "2") (pinfunction "1_2") (pintype "passive"))
    )
    (net (code "4") (name "+VNR") (class "Default")
      (node (ref "C28") (pin "1") (pinfunction "1_1") (pintype "passive"))
      (node (ref "IC5") (pin "8") (pinfunction "VI_8") (pintype "input"))
      (node (ref "R16") (pin "1") (pinfunction "1_1") (pintype "passive"))
    )
    (net (code "5") (name "+VREF") (class "Default")
      (node (ref "C64") (pin "+") (pinfunction "+_+") (pintype "passive"))
      (node (ref "C68") (pin "2") (pinfunction "2_2") (pintype "passive"))
      (node (ref "C79") (pin "2") (pinfunction "2_2") (pintype "passive"))
      (node (ref "IC15") (pin "6") (pinfunction "VOUT_6") (pintype "output"))
      (node (ref "IC16") (pin "2") (pinfunction "VREF_2") (pintype "input"))
      (node (ref "IC18") (pin "9") (pinfunction "REFP0_9") (pintype "input"))
      (node (ref "R31") (pin "1") (pinfunction "1_1") (pintype "passive"))
    )
    (net (code "6") (name "-12V") (class "Default")
      (node (ref "C21") (pin "1") (pinfunction "1_1") (pintype "passive"))
      (node (ref "IC6") (pin "2") (pinfunction "IN_2") (pintype "input"))
      (node (ref "IC6") (pin "3") (pinfunction "IN_3") (pintype "input"))
      (node (ref "IC6") (pin "6") (pinfunction "IN_6") (pintype "input"))
      (node (ref "IC6") (pin "7") (pinfunction "IN_7") (pintype "input"))
      (node (ref "R14") (pin "1") (pinfunction "1_1") (pintype "passive"))
      (node (ref "R39") (pin "2") (pinfunction "2_2") (pintype "passive"))
      (node (ref "R42") (pin "2") (pinfunction "2_2") (pintype "passive"))
    )
    (net (code "7") (name "AUX_USET_SW") (class "Default")
      (node (ref "IC13") (pin "4") (pinfunction "GPB3_4") (pintype "bidirectional"))
      (node (ref "IC17") (pin "6") (pinfunction "CTRL_6") (pintype "input"))
      (node (ref "LED1") (pin "TA") (pinfunction "A_TA") (pintype "passive"))
    )
    (net (code "8") (name "CC_ACTIVE") (class "Default")
      (node (ref "IC13") (pin "22") (pinfunction "GPA1_22") (pintype "bidirectional"))
      (node (ref "Q17") (pin "1") (pinfunction "G_1") (pintype "passive"))
      (node (ref "R97") (pin "1") (pinfunction "1_1") (pintype "passive"))
      (node (ref "R99") (pin "2") (pinfunction "2_2") (pintype "passive"))
    )
    (net (code "9") (name "CSA") (class "Default")
      (node (ref "IC3") (pin "13") (pinfunction "B2_13") (pintype "output"))
      (node (ref "IC4") (pin "1") (pinfunction "A_1") (pintype "input"))
    )
    (net (code "10") (name "CSB") (class "Default")
      (node (ref "IC3") (pin "12") (pinfunction "B3_12") (pintype "output"))
      (node (ref "IC4") (pin "2") (pinfunction "B_2") (pintype "input"))
    )
    (net (code "11") (name "CS_ADC") (class "Default")
      (node (ref "IC18") (pin "2") (pinfunction "~{CS}_2") (pintype "input"))
      (node (ref "RN1") (pin "7") (pinfunction "2_7") (pintype "passive"))
    )
    (net (code "12") (name "CS_DAC") (class "Default")
      (node (ref "IC16") (pin "5") (pinfunction "~{SYNC}_5") (pintype "input"))
      (node (ref "RN1") (pin "8") (pinfunction "2_8") (pintype "passive"))
    )
    (net (code "13") (name "CS_IOEXP") (class "Default")
      (node (ref "IC13") (pin "11") (pinfunction "~{CS}_11") (pintype "input"))
      (node (ref "RN1") (pin "6") (pinfunction "2_6") (pintype "passive"))
    )
    (net (code "14") (name "CURR_5A") (class "Default")
      (node (ref "IC13") (pin "28") (pinfunction "GPA7_28") (pintype "bidirectional"))
      (node (ref "Q12") (pin "4") (pinfunction "G_4") (pintype "passive"))
      (node (ref "R65") (pin "2") (pinfunction "2_2") (pintype "passive"))
    )
    (net (code "15") (name "CURR_50MA") (class "Default")
      (node (ref "IC13") (pin "27") (pinfunction "GPA6_27") (pintype "bidirectional"))
      (node (ref "Q11") (pin "4") (pinfunction "G_4") (pintype "passive"))
      (node (ref "R59") (pin "2") (pinfunction "2_2") (pintype "passive"))
    )
    (net (code "16") (name "CV_ACTIVE") (class "Default")
      (node (ref "IC13") (pin "23") (pinfunction "GPA2_23") (pintype "bidirectional"))
      (node (ref "Q16") (pin "1") (pinfunction "G_1") (pintype "passive"))
      (node (ref "R84") (pin "1") (pinfunction "1_1") (pintype "passive"))
      (node (ref "R86") (pin "2") (pinfunction "2_2") (pintype "passive"))
    )
    (net (code "17") (name "DC+") (class "Default")
      (node (ref "C1") (pin "2") (pinfunction "2_2") (pintype "passive"))
      (node (ref "L1") (pin "1") (pinfunction "1_1") (pintype "passive"))
      (node (ref "R1") (pin "2") (pinfunction "2_2") (pintype "passive"))
      (node (ref "X1") (pin "1") (pinfunction "1_1") (pintype "passive"))
    )
    (net (code "18") (name "DC-") (class "Default")
      (node (ref "C1") (pin "1") (pinfunction "1_1") (pintype "passive"))
      (node (ref "L1") (pin "3") (pinfunction "1_3") (pintype "passive"))
      (node (ref "R1") (pin "1") (pinfunction "1_1") (pintype "passive"))
      (node (ref "X1") (pin "2") (pinfunction "1_2") (pintype "passive"))
    )
    (net (code "19") (name "DC_OUT") (class "Default")
      (node (ref "C2") (pin "+") (pinfunction "+_+") (pintype "passive"))
      (node (ref "C22") (pin "1") (pinfunction "1_1") (pintype "passive"))
      (node (ref "C23") (pin "1") (pinfunction "1_1") (pintype "passive"))
      (node (ref "C4") (pin "2") (pinfunction "2_2") (pintype "passive"))
      (node (ref "C5") (pin "1") (pinfunction "1_1") (pintype "passive"))
      (node (ref "C6") (pin "1") (pinfunction "1_1") (pintype "passive"))
      (node (ref "C7") (pin "1") (pinfunction "1_1") (pintype "passive"))
      (node (ref "C8") (pin "2") (pinfunction "2_2") (pintype "passive"))
      (node (ref "IC1") (pin "11") (pinfunction "VIN_11") (pintype "passive"))
      (node (ref "IC2") (pin "2") (pinfunction "VIN_2") (pintype "power_in"))
      (node (ref "L1") (pin "2") (pinfunction "2_2") (pintype "passive"))
      (node (ref "R15") (pin "2") (pinfunction "2_2") (pintype "passive"))
      (node (ref "R3") (pin "1") (pinfunction "1_1") (pintype "passive"))
      (node (ref "ZD1") (pin "C") (pinfunction "C_C") (pintype "passive"))
    )
    (net (code "20") (name "DIB_A0") (class "Default")
      (node (ref "IC8") (pin "1") (pinfunction "A0_1") (pintype "input"))
      (node (ref "R26") (pin "2") (pinfunction "2_2") (pintype "passive"))
      (node (ref "X2") (pin "17") (pinfunction "1_17") (pintype "passive"))
    )
    (net (code "21") (name "DIB_A1") (class "Default")
      (node (ref "IC8") (pin "2") (pinfunction "A1_2") (pintype "input"))
      (node (ref "R25") (pin "2") (pinfunction "2_2") (pintype "passive"))
      (node (ref "X2") (pin "19") (pinfunction "1_19") (pintype "passive"))
    )
    (net (code "22") (name "DIB_A2") (class "Default")
      (node (ref "IC8") (pin "3") (pinfunction "A2_3") (pintype "input"))
      (node (ref "R24") (pin "2") (pinfunction "2_2") (pintype "passive"))
      (node (ref "X2") (pin "18") (pinfunction "1_18") (pintype "passive"))
    )
    (net (code "23") (name "DIB_CSA") (class "Default")
      (node (ref "IC3") (pin "4") (pinfunction "A2_4") (pintype "input"))
      (node (ref "X2") (pin "9") (pinfunction "1_9") (pintype "passive"))
    )
    (net (code "24") (name "DIB_CSB") (class "Default")
      (node (ref "IC3") (pin "5") (pinfunction "A3_5") (pintype "input"))
      (node (ref "X2") (pin "12") (pinfunction "1_12") (pintype "passive"))
    )
    (net (code "25") (name "DIB_IRQ") (class "Default")
      (node (ref "IC7") (pin "6") (pinfunction "A4_6") (pintype "output"))
      (node (ref "X2") (pin "10") (pinfunction "1_10") (pintype "passive"))
    )
    (net (code "26") (name "DIB_MISO") (class "Default")
      (node (ref "IC3") (pin "6") (pinfunction "A4_6") (pintype "output"))
      (node (ref "X2") (pin "14") (pinfunction "1_14") (pintype "passive"))
    )
    (net (code "27") (name "DIB_MOSI") (class "Default")
      (node (ref "IC7") (pin "3") (pinfunction "A1_3") (pintype "input"))
      (node (ref "X2") (pin "15") (pinfunction "1_15") (pintype "passive"))
    )
    (net (code "28") (name "DIB_NFAULT") (class "Default")
      (node (ref "X2") (pin "3") (pinfunction "1_3") (pintype "passive"))
    )
    (net (code "29") (name "DIB_NRESET") (class "Default")
      (node (ref "IC7") (pin "5") (pinfunction "A3_5") (pintype "input"))
      (node (ref "X2") (pin "4") (pinfunction "1_4") (pintype "passive"))
    )
    (net (code "30") (name "DIB_SCL") (class "Default")
      (node (ref "IC8") (pin "6") (pinfunction "SCL_6") (pintype "bidirectional"))
      (node (ref "X2") (pin "5") (pinfunction "1_5") (pintype "passive"))
    )
    (net (code "31") (name "DIB_SCLK") (class "Default")
      (node (ref "IC3") (pin "3") (pinfunction "A1_3") (pintype "input"))
      (node (ref "X2") (pin "13") (pinfunction "1_13") (pintype "passive"))
    )
    (net (code "32") (name "DIB_SDA") (class "Default")
      (node (ref "IC8") (pin "5") (pinfunction "SDA_5") (pintype "bidirectional"))
      (node (ref "X2") (pin "8") (pinfunction "1_8") (pintype "passive"))
    )
    (net (code "33") (name "FB") (class "Default")
      (node (ref "C19") (pin "1") (pinfunction "1_1") (pintype "passive"))
      (node (ref "IC1") (pin "5") (pinfunction "VFB_5") (pintype "input"))
      (node (ref "Q2") (pin "C") (pinfunction "C_C") (pintype "passive"))
      (node (ref "R11") (pin "2") (pinfunction "2_2") (pintype "passive"))
      (node (ref "R13") (pin "1") (pinfunction "1_1") (pintype "passive"))
    )
    (net (code "34") (name "GCOM") (class "Default")
      (node (ref "IC10") (pin "6") (pinfunction "-IN_6") (pintype "input"))
      (node (ref "IC10") (pin "7") (pinfunction "OUT_7") (pintype "output"))
      (node (ref "R40") (pin "1") (pinfunction "1_1") (pintype "passive"))
      (node (ref "R57") (pin "1") (pinfunction "1_1") (pintype "passive"))
    )
    (net (code "35") (name "GND") (class "Default")
      (node (ref "C20") (pin "2") (pinfunction "2_2") (pintype "passive"))
      (node (ref "C21") (pin "2") (pinfunction "2_2") (pintype "passive"))
      (node (ref "C22") (pin "2") (pinfunction "2_2") (pintype "passive"))
      (node (ref "C23") (pin "2") (pinfunction "2_2") (pintype "passive"))
      (node (ref "C26") (pin "2") (pinfunction "2_2") (pintype "passive"))
      (node (ref "C27") (pin "2") (pinfunction "2_2") (pintype "passive"))
      (node (ref "C28") (pin "2") (pinfunction "2_2") (pintype "passive"))
      (node (ref "C29") (pin "2") (pinfunction "2_2") (pintype "passive"))
      (node (ref "C30") (pin "1") (pinfunction "1_1") (pintype "passive"))
      (node (ref "C32") (pin "1") (pinfunction "1_1") (pintype "passive"))
      (node (ref "C33") (pin "2") (pinfunction "2_2") (pintype "passive"))
      (node (ref "C34") (pin "1") (pinfunction "1_1") (pintype "passive"))
      (node (ref "C35") (pin "2") (pinfunction "2_2") (pintype "passive"))
      (node (ref "C37") (pin "1") (pinfunction "1_1") (pintype "passive"))
      (node (ref "C38") (pin "1") (pinfunction "1_1") (pintype "passive"))
      (node (ref "C40") (pin "2") (pinfunction "2_2") (pintype "passive"))
      (node (ref "C48") (pin "1") (pinfunction "1_1") (pintype "passive"))
      (node (ref "C49") (pin "2") (pinfunction "2_2") (pintype "passive"))
      (node (ref "C50") (pin "1") (pinfunction "1_1") (pintype "passive"))
      (node (ref "C51") (pin "1") (pinfunction "1_1") (pintype "passive"))
      (node (ref "C52") (pin "1") (pinfunction "1_1") (pintype "passive"))
      (node (ref "C53") (pin "1") (pinfunction "1_1") (pintype "passive"))
      (node (ref "C55") (pin "1") (pinfunction "1_1") (pintype "passive"))
      (node (ref "C56") (pin "2") (pinfunction "2_2") (pintype "passive"))
      (node (ref "C57") (pin "1") (pinfunction "1_1") (pintype "passive"))
      (node (ref "C58") (pin "1") (pinfunction "1_1") (pintype "passive"))
      (node (ref "C60") (pin "2") (pinfunction "2_2") (pintype "passive"))
      (node (ref "C61") (pin "1") (pinfunction "1_1") (pintype "passive"))
      (node (ref "C62") (pin "2") (pinfunction "2_2") (pintype "passive"))
      (node (ref "C63") (pin "2") (pinfunction "2_2") (pintype "passive"))
      (node (ref "C64") (pin "-") (pinfunction "-_-") (pintype "passive"))
      (node (ref "C65") (pin "2") (pinfunction "2_2") (pintype "passive"))
      (node (ref "C66") (pin "2") (pinfunction "2_2") (pintype "passive"))
      (node (ref "C67") (pin "1") (pinfunction "1_1") (pintype "passive"))
      (node (ref "C68") (pin "1") (pinfunction "1_1") (pintype "passive"))
      (node (ref "C69") (pin "2") (pinfunction "2_2") (pintype "passive"))
      (node (ref "C70") (pin "1") (pinfunction "1_1") (pintype "passive"))
      (node (ref "C71") (pin "1") (pinfunction "1_1") (pintype "passive"))
      (node (ref "C72") (pin "1") (pinfunction "1_1") (pintype "passive"))
      (node (ref "C73") (pin "2") (pinfunction "2_2") (pintype "passive"))
      (node (ref "C74") (pin "1") (pinfunction "1_1") (pintype "passive"))
      (node (ref "C75") (pin "1") (pinfunction "1_1") (pintype "passive"))
      (node (ref "C76") (pin "1") (pinfunction "1_1") (pintype "passive"))
      (node (ref "C77") (pin "1") (pinfunction "1_1") (pintype "passive"))
      (node (ref "C78") (pin "1") (pinfunction "1_1") (pintype "passive"))
      (node (ref "C79") (pin "1") (pinfunction "1_1") (pintype "passive"))
      (node (ref "C80") (pin "1") (pinfunction "1_1") (pintype "passive"))
      (node (ref "C81") (pin "2") (pinfunction "2_2") (pintype "passive"))
      (node (ref "C82") (pin "1") (pinfunction "1_1") (pintype "passive"))
      (node (ref "C83") (pin "1") (pinfunction "1_1") (pintype "passive"))
      (node (ref "C84") (pin "1") (pinfunction "1_1") (pintype "passive"))
      (node (ref "C85") (pin "1") (pinfunction "1_1") (pintype "passive"))
      (node (ref "D19") (pin "C") (pinfunction "C_C") (pintype "passive"))
      (node (ref "D5") (pin "A") (pinfunction "A_A") (pintype "passive"))
      (node (ref "D6") (pin "A") (pinfunction "A_A") (pintype "passive"))
      (node (ref "D7") (pin "C") (pinfunction "C_C") (pintype "passive"))
      (node (ref "GND") (pin "1") (pinfunction "P$1_1") (pintype "bidirectional"))
      (node (ref "IC12") (pin "4") (pinfunction "VSS_4") (pintype "power_in"))
      (node (ref "IC13") (pin "10") (pinfunction "VSS_10") (pintype "power_in"))
      (node (ref "IC13") (pin "15") (pinfunction "A0_15") (pintype "input"))
      (node (ref "IC13") (pin "16") (pinfunction "A1_16") (pintype "input"))
      (node (ref "IC13") (pin "17") (pinfunction "A2_17") (pintype "input"))
      (node (ref "IC14") (pin "2") (pinfunction "GND_2") (pintype "passive"))
      (node (ref "IC15") (pin "4") (pinfunction "GND_4") (pintype "passive"))
      (node (ref "IC16") (pin "8") (pinfunction "GND_8") (pintype "power_in"))
      (node (ref "IC17") (pin "2") (pinfunction "GND_2") (pintype "passive"))
      (node (ref "IC18") (pin "3") (pinfunction "CLK_3") (pintype "bidirectional"))
      (node (ref "IC18") (pin "4") (pinfunction "DGND_4") (pintype "passive"))
      (node (ref "IC18") (pin "5") (pinfunction "AVSS_5") (pintype "passive"))
      (node (ref "IC18") (pin "8") (pinfunction "REFN0_8") (pintype "input"))
      (node (ref "IC2") (pin "9") (pinfunction "GND_9") (pintype "passive"))
      (node (ref "IC2") (pin "TP") (pinfunction "TP_TP") (pintype "passive"))
      (node (ref "IC20") (pin "4") (pinfunction "GND_4") (pintype "passive"))
      (node (ref "IC3") (pin "15") (pinfunction "GND2_15") (pintype "passive"))
      (node (ref "IC3") (pin "9") (pinfunction "GND2_2_9") (pintype "passive"))
      (node (ref "IC4") (pin "4") (pinfunction "GND_4") (pintype "passive"))
      (node (ref "IC5") (pin "2") (pinfunction "GND_2") (pintype "passive"))
      (node (ref "IC5") (pin "3") (pinfunction "GND_3") (pintype "passive"))
      (node (ref "IC5") (pin "6") (pinfunction "GND_6") (pintype "passive"))
      (node (ref "IC5") (pin "7") (pinfunction "GND_7") (pintype "passive"))
      (node (ref "IC6") (pin "5") (pinfunction "GND_5") (pintype "passive"))
      (node (ref "IC7") (pin "15") (pinfunction "GND2_15") (pintype "passive"))
      (node (ref "IC7") (pin "9") (pinfunction "GND2_2_9") (pintype "passive"))
      (node (ref "KK3") (pin "1") (pinfunction "1_1") (pintype "passive"))
      (node (ref "KK3") (pin "2") (pinfunction "2_2") (pintype "passive"))
      (node (ref "Q10") (pin "2") (pinfunction "S_2") (pintype "passive"))
      (node (ref "Q16") (pin "2") (pinfunction "S_2") (pintype "passive"))
      (node (ref "Q17") (pin "2") (pinfunction "S_2") (pintype "passive"))
      (node (ref "Q18") (pin "2") (pinfunction "S_2") (pintype "passive"))
      (node (ref "Q19") (pin "E") (pinfunction "E_E") (pintype "passive"))
      (node (ref "Q21") (pin "E") (pinfunction "E_E") (pintype "passive"))
      (node (ref "Q23") (pin "2") (pinfunction "S_2") (pintype "passive"))
      (node (ref "R103") (pin "1") (pinfunction "1_1") (pintype "passive"))
      (node (ref "R112") (pin "1") (pinfunction "1_1") (pintype "passive"))
      (node (ref "R115") (pin "1") (pinfunction "1_1") (pintype "passive"))
      (node (ref "R17") (pin "1") (pinfunction "1_1") (pintype "passive"))
      (node (ref "R18") (pin "1") (pinfunction "1_1") (pintype "passive"))
      (node (ref "R21") (pin "1") (pinfunction "1_1") (pintype "passive"))
      (node (ref "R23") (pin "1") (pinfunction "1_1") (pintype "passive"))
      (node (ref "R36") (pin "2") (pinfunction "2_2") (pintype "passive"))
      (node (ref "R56") (pin "1") (pinfunction "1_1") (pintype "passive"))
      (node (ref "R59") (pin "1") (pinfunction "1_1") (pintype "passive"))
      (node (ref "R65") (pin "1") (pinfunction "1_1") (pintype "passive"))
      (node (ref "R71") (pin "1") (pinfunction "1_1") (pintype "passive"))
      (node (ref "R72") (pin "2") (pinfunction "2_2") (pintype "passive"))
      (node (ref "R87") (pin "2") (pinfunction "2_2") (pintype "passive"))
      (node (ref "R91") (pin "1") (pinfunction "1_1") (pintype "passive"))
      (node (ref "R94") (pin "1") (pinfunction "1_1") (pintype "passive"))
      (node (ref "R95") (pin "1") (pinfunction "1_1") (pintype "passive"))
      (node (ref "R96") (pin "2") (pinfunction "2_2") (pintype "passive"))
      (node (ref "SH1") (pin "2") (pinfunction "GND_B_2") (pintype "bidirectional"))
      (node (ref "TR1") (pin "4") (pinfunction "4_4") (pintype "passive"))
      (node (ref "X3") (pin "2") (pinfunction "1_2") (pintype "passive"))
      (node (ref "ZD2") (pin "1") (pinfunction "A_1") (pintype "passive"))
      (node (ref "ZD2") (pin "2") (pinfunction "A_2") (pintype "passive"))
    )
    (net (code "36") (name "GNDIO") (class "Default")
      (node (ref "C31") (pin "2") (pinfunction "2_2") (pintype "passive"))
      (node (ref "C36") (pin "2") (pinfunction "2_2") (pintype "passive"))
      (node (ref "C39") (pin "1") (pinfunction "1_1") (pintype "passive"))
      (node (ref "IC3") (pin "2") (pinfunction "GND1_2_2") (pintype "passive"))
      (node (ref "IC3") (pin "8") (pinfunction "GND1_8") (pintype "passive"))
      (node (ref "IC7") (pin "2") (pinfunction "GND1_2_2") (pintype "passive"))
      (node (ref "IC7") (pin "8") (pinfunction "GND1_8") (pintype "passive"))
      (node (ref "IC8") (pin "4") (pinfunction "GND_4") (pintype "passive"))
      (node (ref "IC8") (pin "7") (pinfunction "WP_7") (pintype "input"))
      (node (ref "X2") (pin "11") (pinfunction "1_11") (pintype "passive"))
      (node (ref "X2") (pin "16") (pinfunction "1_16") (pintype "passive"))
      (node (ref "X2") (pin "20") (pinfunction "1_20") (pintype "passive"))
      (node (ref "X2") (pin "25") (pinfunction "1_25") (pintype "passive"))
      (node (ref "X2") (pin "7") (pinfunction "1_7") (pintype "passive"))
    )
    (net (code "37") (name "IRQ") (class "Default")
      (node (ref "IC13") (pin "20") (pinfunction "INTA_20") (pintype "output"))
      (node (ref "RN2") (pin "5") (pinfunction "2_5") (pintype "passive"))
    )
    (net (code "38") (name "ISENSE+") (class "Default")
      (node (ref "IC11") (pin "3") (pinfunction "+IN_3") (pintype "input"))
      (node (ref "R57") (pin "2") (pinfunction "2_2") (pintype "passive"))
      (node (ref "R58") (pin "2") (pinfunction "2_2") (pintype "passive"))
    )
    (net (code "39") (name "ISENSE-") (class "Default")
      (node (ref "IC11") (pin "2") (pinfunction "-IN_2") (pintype "input"))
      (node (ref "R64") (pin "1") (pinfunction "1_1") (pintype "passive"))
      (node (ref "R68") (pin "2") (pinfunction "2_2") (pintype "passive"))
    )
    (net (code "40") (name "I_MON") (class "Default")
      (node (ref "IC11") (pin "6") (pinfunction "OUT_6") (pintype "output"))
      (node (ref "R62") (pin "1") (pinfunction "1_1") (pintype "passive"))
      (node (ref "R64") (pin "2") (pinfunction "2_2") (pintype "passive"))
      (node (ref "R79") (pin "1") (pinfunction "1_1") (pintype "passive"))
    )
    (net (code "41") (name "I_SERVO") (class "Default")
      (node (ref "C54") (pin "2") (pinfunction "2_2") (pintype "passive"))
      (node (ref "D13") (pin "C") (pinfunction "C_C") (pintype "passive"))
      (node (ref "D15") (pin "A") (pinfunction "A_A") (pintype "passive"))
      (node (ref "IC10") (pin "1") (pinfunction "OUT_1") (pintype "output"))
      (node (ref "R100") (pin "1") (pinfunction "1_1") (pintype "passive"))
    )
    (net (code "42") (name "I_SET") (class "Default")
      (node (ref "I_SET") (pin "2") (pinfunction "2_2") (pintype "passive"))
      (node (ref "R60") (pin "1") (pinfunction "1_1") (pintype "passive"))
      (node (ref "R76") (pin "1") (pinfunction "1_1") (pintype "passive"))
    )
    (net (code "43") (name "MISO") (class "Default")
      (node (ref "IC13") (pin "14") (pinfunction "SO_14") (pintype "output"))
      (node (ref "IC14") (pin "4") (pinfunction "SI/O_4") (pintype "bidirectional"))
      (node (ref "IC18") (pin "15") (pinfunction "DOUT/~{DRDY}_15") (pintype "output"))
      (node (ref "RN2") (pin "8") (pinfunction "2_8") (pintype "passive"))
    )
    (net (code "44") (name "MOSI") (class "Default")
      (node (ref "IC13") (pin "13") (pinfunction "SI_13") (pintype "input"))
      (node (ref "IC16") (pin "7") (pinfunction "DIN_7") (pintype "input"))
      (node (ref "IC18") (pin "16") (pinfunction "DIN_16") (pintype "input"))
      (node (ref "RN2") (pin "7") (pinfunction "2_7") (pintype "passive"))
    )
    (net (code "45") (name "Net-(C10-Pad1)") (class "Default")
      (node (ref "C10") (pin "1") (pinfunction "1_1") (pintype "passive"))
      (node (ref "C11") (pin "+") (pinfunction "+_+") (pintype "passive"))
      (node (ref "C15") (pin "1") (pinfunction "1_1") (pintype "passive"))
      (node (ref "C16") (pin "+") (pinfunction "+_+") (pintype "passive"))
      (node (ref "L2") (pin "2") (pinfunction "2_2") (pintype "passive"))
      (node (ref "L3") (pin "1") (pinfunction "1_1") (pintype "passive"))
      (node (ref "R11") (pin "1") (pinfunction "1_1") (pintype "passive"))
      (node (ref "R6") (pin "1") (pinfunction "1_1") (pintype "passive"))
      (node (ref "R8") (pin "1") (pinfunction "1_1") (pintype "passive"))
      (node (ref "R9") (pin "1") (pinfunction "1_1") (pintype "passive"))
    )
    (net (code "46") (name "Net-(C12-Pad2)") (class "Default")
      (node (ref "C12") (pin "2") (pinfunction "2_2") (pintype "passive"))
      (node (ref "R7") (pin "2") (pinfunction "2_2") (pintype "passive"))
    )
    (net (code "47") (name "Net-(C18-Pad1)") (class "Default")
      (node (ref "C18") (pin "1") (pinfunction "1_1") (pintype "passive"))
      (node (ref "R10") (pin "1") (pinfunction "1_1") (pintype "passive"))
    )
    (net (code "48") (name "Net-(C19-Pad2)") (class "Default")
      (node (ref "C19") (pin "2") (pinfunction "2_2") (pintype "passive"))
      (node (ref "D3") (pin "A") (pinfunction "A_A") (pintype "passive"))
      (node (ref "Q2") (pin "B") (pinfunction "B_B") (pintype "passive"))
      (node (ref "R12") (pin "1") (pinfunction "1_1") (pintype "passive"))
      (node (ref "R9") (pin "2") (pinfunction "2_2") (pintype "passive"))
    )
    (net (code "49") (name "Net-(C20-Pad1)") (class "Default")
      (node (ref "C20") (pin "1") (pinfunction "1_1") (pintype "passive"))
      (node (ref "D4") (pin "A") (pinfunction "A_A") (pintype "passive"))
      (node (ref "R14") (pin "2") (pinfunction "2_2") (pintype "passive"))
    )
    (net (code "50") (name "Net-(C25-Pad2)") (class "Default")
      (node (ref "C25") (pin "2") (pinfunction "2_2") (pintype "passive"))
      (node (ref "R17") (pin "2") (pinfunction "2_2") (pintype "passive"))
    )
    (net (code "51") (name "Net-(C26-Pad1)") (class "Default")
      (node (ref "C26") (pin "1") (pinfunction "1_1") (pintype "passive"))
      (node (ref "C27") (pin "1") (pinfunction "1_1") (pintype "passive"))
      (node (ref "R16") (pin "2") (pinfunction "2_2") (pintype "passive"))
      (node (ref "R20") (pin "2") (pinfunction "2_2") (pintype "passive"))
      (node (ref "TR1") (pin "3") (pinfunction "3_3") (pintype "passive"))
    )
    (net (code "52") (name "Net-(C34-Pad2)") (class "Default")
      (node (ref "C34") (pin "2") (pinfunction "2_2") (pintype "passive"))
      (node (ref "R22") (pin "1") (pinfunction "1_1") (pintype "passive"))
    )
    (net (code "53") (name "Net-(C41-Pad2)") (class "Default")
      (node (ref "C41") (pin "2") (pinfunction "2_2") (pintype "passive"))
      (node (ref "R41") (pin "1") (pinfunction "1_1") (pintype "passive"))
    )
    (net (code "54") (name "Net-(C42-Pad1)") (class "Default")
      (node (ref "C42") (pin "1") (pinfunction "1_1") (pintype "passive"))
      (node (ref "R44") (pin "2") (pinfunction "2_2") (pintype "passive"))
      (node (ref "R45") (pin "1") (pinfunction "1_1") (pintype "passive"))
    )
    (net (code "55") (name "Net-(C43-Pad2)") (class "Default")
      (node (ref "C43") (pin "2") (pinfunction "2_2") (pintype "passive"))
      (node (ref "R46") (pin "1") (pinfunction "1_1") (pintype "passive"))
    )
    (net (code "56") (name "Net-(C44-Pad1)") (class "Default")
      (node (ref "C44") (pin "1") (pinfunction "1_1") (pintype "passive"))
      (node (ref "R50") (pin "2") (pinfunction "2_2") (pintype "passive"))
      (node (ref "R51") (pin "1") (pinfunction "1_1") (pintype "passive"))
    )
    (net (code "57") (name "Net-(C45-Pad1)") (class "Default")
      (node (ref "C45") (pin "1") (pinfunction "1_1") (pintype "passive"))
      (node (ref "R53") (pin "2") (pinfunction "2_2") (pintype "passive"))
    )
    (net (code "58") (name "Net-(C46-Pad2)") (class "Default")
      (node (ref "C46") (pin "2") (pinfunction "2_2") (pintype "passive"))
      (node (ref "R54") (pin "1") (pinfunction "1_1") (pintype "passive"))
    )
    (net (code "59") (name "Net-(C47-Pad2)") (class "Default")
      (node (ref "C47") (pin "2") (pinfunction "2_2") (pintype "passive"))
      (node (ref "R55") (pin "1") (pinfunction "1_1") (pintype "passive"))
    )
    (net (code "60") (name "Net-(C54-Pad1)") (class "Default")
      (node (ref "C54") (pin "1") (pinfunction "1_1") (pintype "passive"))
      (node (ref "R63") (pin "1") (pinfunction "1_1") (pintype "passive"))
    )
    (net (code "61") (name "Net-(C59-Pad2)") (class "Default")
      (node (ref "C59") (pin "2") (pinfunction "2_2") (pintype "passive"))
      (node (ref "R66") (pin "1") (pinfunction "1_1") (pintype "passive"))
    )
    (net (code "62") (name "Net-(C86-Pad2)") (class "Default")
      (node (ref "C86") (pin "2") (pinfunction "2_2") (pintype "passive"))
      (node (ref "Q20") (pin "B") (pinfunction "B_B") (pintype "passive"))
      (node (ref "R102") (pin "1") (pinfunction "1_1") (pintype "passive"))
      (node (ref "R105") (pin "2") (pinfunction "2_2") (pintype "passive"))
      (node (ref "R107") (pin "2") (pinfunction "2_2") (pintype "passive"))
    )
    (net (code "63") (name "Net-(C87-Pad1)") (class "Default")
      (node (ref "C87") (pin "1") (pinfunction "1_1") (pintype "passive"))
      (node (ref "Q19") (pin "B") (pinfunction "B_B") (pintype "passive"))
      (node (ref "R103") (pin "2") (pinfunction "2_2") (pintype "passive"))
      (node (ref "R104") (pin "2") (pinfunction "2_2") (pintype "passive"))
    )
    (net (code "64") (name "Net-(C87-Pad2)") (class "Default")
      (node (ref "C87") (pin "2") (pinfunction "2_2") (pintype "passive"))
      (node (ref "Q20") (pin "C") (pinfunction "C_C") (pintype "passive"))
      (node (ref "R104") (pin "1") (pinfunction "1_1") (pintype "passive"))
      (node (ref "R109") (pin "2") (pinfunction "2_2") (pintype "passive"))
    )
    (net (code "65") (name "Net-(C88-Pad2)") (class "Default")
      (node (ref "C88") (pin "2") (pinfunction "2_2") (pintype "passive"))
      (node (ref "R110") (pin "2") (pinfunction "2_2") (pintype "passive"))
    )
    (net (code "66") (name "Net-(C95-Pad1)") (class "Default")
      (node (ref "C95") (pin "1") (pinfunction "1_1") (pintype "passive"))
      (node (ref "Q22") (pin "B") (pinfunction "B_B") (pintype "passive"))
      (node (ref "R111") (pin "1") (pinfunction "1_1") (pintype "passive"))
      (node (ref "R113") (pin "2") (pinfunction "2_2") (pintype "passive"))
    )
    (net (code "67") (name "Net-(D2-C)") (class "Default")
      (node (ref "C12") (pin "1") (pinfunction "1_1") (pintype "passive"))
      (node (ref "D2") (pin "3") (pinfunction "C_3") (pintype "passive"))
      (node (ref "L2") (pin "1") (pinfunction "1_1") (pintype "passive"))
      (node (ref "Q1") (pin "2") (pinfunction "D_2") (pintype "passive"))
    )
    (net (code "68") (name "Net-(D3-PadC)") (class "Default")
      (node (ref "D3") (pin "C") (pinfunction "C_C") (pintype "passive"))
      (node (ref "Q2") (pin "E") (pinfunction "E_E") (pintype "passive"))
      (node (ref "R8") (pin "2") (pinfunction "2_2") (pintype "passive"))
    )
    (net (code "69") (name "Net-(D4-PadC)") (class "Default")
      (node (ref "D4") (pin "C") (pinfunction "C_C") (pintype "passive"))
      (node (ref "TR1") (pin "2") (pinfunction "2_2") (pintype "passive"))
    )
    (net (code "70") (name "Net-(D8-PadC)") (class "Default")
      (node (ref "D8") (pin "C") (pinfunction "C_C") (pintype "passive"))
      (node (ref "D9") (pin "C") (pinfunction "C_C") (pintype "passive"))
      (node (ref "Q8") (pin "2") (pinfunction "C_2") (pintype "passive"))
      (node (ref "Q8") (pin "4") (pinfunction "C_4") (pintype "passive"))
      (node (ref "R35") (pin "1") (pinfunction "1_1") (pintype "passive"))
    )
    (net (code "71") (name "Net-(D10-PadA)") (class "Default")
      (node (ref "D10") (pin "A") (pinfunction "A_A") (pintype "passive"))
      (node (ref "Q6") (pin "E") (pinfunction "E_E") (pintype "passive"))
      (node (ref "R32") (pin "1") (pinfunction "1_1") (pintype "passive"))
      (node (ref "R33") (pin "1") (pinfunction "1_1") (pintype "passive"))
    )
    (net (code "72") (name "Net-(D10-PadC)") (class "Default")
      (node (ref "D10") (pin "C") (pinfunction "C_C") (pintype "passive"))
      (node (ref "R38") (pin "2") (pinfunction "2_2") (pintype "passive"))
    )
    (net (code "73") (name "Net-(D18-PadA)") (class "Default")
      (node (ref "D18") (pin "A") (pinfunction "A_A") (pintype "passive"))
      (node (ref "Q15") (pin "B") (pinfunction "B_B") (pintype "passive"))
      (node (ref "R89") (pin "1") (pinfunction "1_1") (pintype "passive"))
      (node (ref "R94") (pin "2") (pinfunction "2_2") (pintype "passive"))
    )
    (net (code "74") (name "Net-(D18-PadC)") (class "Default")
      (node (ref "D18") (pin "C") (pinfunction "C_C") (pintype "passive"))
      (node (ref "D19") (pin "A") (pinfunction "A_A") (pintype "passive"))
    )
    (net (code "75") (name "Net-(D20-C)") (class "Default")
      (node (ref "C86") (pin "1") (pinfunction "1_1") (pintype "passive"))
      (node (ref "C88") (pin "1") (pinfunction "1_1") (pintype "passive"))
      (node (ref "C89") (pin "+") (pinfunction "+_+") (pintype "passive"))
      (node (ref "D20") (pin "3") (pinfunction "C_3") (pintype "passive"))
      (node (ref "F1") (pin "2") (pinfunction "2_2") (pintype "passive"))
      (node (ref "F2") (pin "1") (pinfunction "1_1") (pintype "passive"))
      (node (ref "JP4") (pin "2") (pinfunction "2_2") (pintype "passive"))
      (node (ref "K1") (pin "2") (pinfunction "O_2") (pintype "passive"))
      (node (ref "Q20") (pin "E") (pinfunction "E_E") (pintype "passive"))
      (node (ref "R102") (pin "2") (pinfunction "2_2") (pintype "passive"))
    )
    (net (code "76") (name "Net-(FB1-1)") (class "Default")
      (node (ref "C35") (pin "1") (pinfunction "1_1") (pintype "passive"))
      (node (ref "D6") (pin "C") (pinfunction "C_C") (pintype "passive"))
      (node (ref "FB1") (pin "P$1") (pinfunction "1_P$1") (pintype "passive"))
      (node (ref "FB2") (pin "P$1") (pinfunction "1_P$1") (pintype "passive"))
      (node (ref "IC5") (pin "1") (pinfunction "VO_1") (pintype "passive"))
    )
    (net (code "77") (name "Net-(FB3-1)") (class "Default")
      (node (ref "C38") (pin "2") (pinfunction "2_2") (pintype "passive"))
      (node (ref "D7") (pin "A") (pinfunction "A_A") (pintype "passive"))
      (node (ref "FB3") (pin "P$1") (pinfunction "1_P$1") (pintype "passive"))
      (node (ref "IC6") (pin "1") (pinfunction "OUT_1") (pintype "passive"))
    )
    (net (code "78") (name "Net-(IC1-CAP)") (class "Default")
      (node (ref "C8") (pin "1") (pinfunction "1_1") (pintype "passive"))
      (node (ref "IC1") (pin "9") (pinfunction "CAP_9") (pintype "passive"))
    )
    (net (code "79") (name "Net-(IC1-FREQ)") (class "Default")
      (node (ref "IC1") (pin "2") (pinfunction "FREQ_2") (pintype "input"))
      (node (ref "R4") (pin "1") (pinfunction "1_1") (pintype "passive"))
    )
    (net (code "80") (name "Net-(IC1-GATE)") (class "Default")
      (node (ref "IC1") (pin "12") (pinfunction "GATE_12") (pintype "output"))
      (node (ref "R5") (pin "1") (pinfunction "1_1") (pintype "passive"))
    )
    (net (code "81") (name "Net-(IC1-ITH)") (class "Default")
      (node (ref "C17") (pin "1") (pinfunction "1_1") (pintype "passive"))
      (node (ref "IC1") (pin "6") (pinfunction "ITH_6") (pintype "bidirectional"))
      (node (ref "R10") (pin "2") (pinfunction "2_2") (pintype "passive"))
    )
    (net (code "82") (name "Net-(IC1-RUN)") (class "Default")
      (node (ref "D1") (pin "C") (pinfunction "C_C") (pintype "passive"))
      (node (ref "IC1") (pin "8") (pinfunction "RUN_8") (pintype "input"))
      (node (ref "R2") (pin "2") (pinfunction "2_2") (pintype "passive"))
    )
    (net (code "83") (name "Net-(IC1-SENSE)") (class "Default")
      (node (ref "IC1") (pin "10") (pinfunction "SENSE_10") (pintype "input"))
      (node (ref "Q1") (pin "3") (pinfunction "S_3") (pintype "passive"))
      (node (ref "R3") (pin "2") (pinfunction "2_2") (pintype "passive"))
    )
    (net (code "84") (name "Net-(IC1-SS)") (class "Default")
      (node (ref "C9") (pin "2") (pinfunction "2_2") (pintype "passive"))
      (node (ref "IC1") (pin "4") (pinfunction "SS_4") (pintype "input"))
    )
    (net (code "85") (name "Net-(IC2-BOOT)") (class "Default")
      (node (ref "C24") (pin "2") (pinfunction "2_2") (pintype "passive"))
      (node (ref "IC2") (pin "1") (pinfunction "BOOT_1") (pintype "output"))
    )
    (net (code "86") (name "Net-(IC2-COMP)") (class "Default")
      (node (ref "C30") (pin "2") (pinfunction "2_2") (pintype "passive"))
      (node (ref "IC2") (pin "8") (pinfunction "COMP_8") (pintype "output"))
      (node (ref "R22") (pin "2") (pinfunction "2_2") (pintype "passive"))
    )
    (net (code "87") (name "Net-(IC2-EN)") (class "Default")
      (node (ref "IC2") (pin "3") (pinfunction "EN_3") (pintype "input"))
      (node (ref "R15") (pin "1") (pinfunction "1_1") (pintype "passive"))
      (node (ref "R18") (pin "2") (pinfunction "2_2") (pintype "passive"))
    )
    (net (code "88") (name "Net-(IC2-PH)") (class "Default")
      (node (ref "C24") (pin "1") (pinfunction "1_1") (pintype "passive"))
      (node (ref "C25") (pin "1") (pinfunction "1_1") (pintype "passive"))
      (node (ref "D5") (pin "C") (pinfunction "C_C") (pintype "passive"))
      (node (ref "IC2") (pin "10") (pinfunction "PH_10") (pintype "input"))
      (node (ref "TR1") (pin "1") (pinfunction "1_1") (pintype "passive"))
    )
    (net (code "89") (name "Net-(IC2-RT{slash}CLK)") (class "Default")
      (node (ref "IC2") (pin "5") (pinfunction "RT/CLK_5") (pintype "input"))
      (node (ref "R21") (pin "2") (pinfunction "2_2") (pintype "passive"))
    )
    (net (code "90") (name "Net-(IC2-SS{slash}TR)") (class "Default")
      (node (ref "C29") (pin "1") (pinfunction "1_1") (pintype "passive"))
      (node (ref "IC2") (pin "4") (pinfunction "SS/TR_4") (pintype "input"))
    )
    (net (code "91") (name "Net-(IC2-VSENSE)") (class "Default")
      (node (ref "IC2") (pin "7") (pinfunction "VSENSE_7") (pintype "input"))
      (node (ref "R20") (pin "1") (pinfunction "1_1") (pintype "passive"))
      (node (ref "R23") (pin "2") (pinfunction "2_2") (pintype "passive"))
    )
    (net (code "92") (name "Net-(IC3-B1)") (class "Default")
      (node (ref "IC3") (pin "14") (pinfunction "B1_14") (pintype "output"))
      (node (ref "RN1") (pin "4") (pinfunction "1_4") (pintype "passive"))
    )
    (net (code "93") (name "Net-(IC3-B4)") (class "Default")
      (node (ref "IC3") (pin "11") (pinfunction "B4_11") (pintype "input"))
      (node (ref "RN2") (pin "1") (pinfunction "1_1") (pintype "passive"))
    )
    (net (code "94") (name "Net-(IC4-Y0)") (class "Default")
      (node (ref "IC4") (pin "7") (pinfunction "Y0_7") (pintype "output"))
      (node (ref "RN1") (pin "1") (pinfunction "1_1") (pintype "passive"))
    )
    (net (code "95") (name "Net-(IC4-Y1)") (class "Default")
      (node (ref "IC4") (pin "6") (pinfunction "Y1_6") (pintype "output"))
      (node (ref "RN1") (pin "2") (pinfunction "1_2") (pintype "passive"))
    )
    (net (code "96") (name "Net-(IC4-Y2)") (class "Default")
      (node (ref "IC4") (pin "5") (pinfunction "Y2_5") (pintype "output"))
      (node (ref "RN1") (pin "3") (pinfunction "1_3") (pintype "passive"))
    )
    (net (code "97") (name "Net-(IC7-B1)") (class "Default")
      (node (ref "IC7") (pin "14") (pinfunction "B1_14") (pintype "output"))
      (node (ref "RN2") (pin "2") (pinfunction "1_2") (pintype "passive"))
    )
    (net (code "98") (name "Net-(IC7-B2)") (class "Default")
      (node (ref "IC7") (pin "13") (pinfunction "B2_13") (pintype "output"))
      (node (ref "RN2") (pin "3") (pinfunction "1_3") (pintype "passive"))
    )
    (net (code "99") (name "Net-(IC7-B4)") (class "Default")
      (node (ref "IC7") (pin "11") (pinfunction "B4_11") (pintype "input"))
      (node (ref "RN2") (pin "4") (pinfunction "1_4") (pintype "passive"))
    )
    (net (code "100") (name "Net-(IC9A-+IN)") (class "Default")
      (node (ref "IC9") (pin "3") (pinfunction "+IN_3") (pintype "input"))
      (node (ref "R46") (pin "2") (pinfunction "2_2") (pintype "passive"))
      (node (ref "R47") (pin "2") (pinfunction "2_2") (pintype "passive"))
    )
    (net (code "101") (name "Net-(IC9A--IN)") (class "Default")
      (node (ref "D12") (pin "C") (pinfunction "C_C") (pintype "passive"))
      (node (ref "IC9") (pin "2") (pinfunction "-IN_2") (pintype "input"))
      (node (ref "R48") (pin "2") (pinfunction "2_2") (pintype "passive"))
      (node (ref "R53") (pin "1") (pinfunction "1_1") (pintype "passive"))
      (node (ref "R55") (pin "2") (pinfunction "2_2") (pintype "passive"))
    )
    (net (code "102") (name "Net-(IC9B-+IN)") (class "Default")
      (node (ref "IC9") (pin "5") (pinfunction "+IN_5") (pintype "input"))
      (node (ref "R40") (pin "2") (pinfunction "2_2") (pintype "passive"))
      (node (ref "R41") (pin "2") (pinfunction "2_2") (pintype "passive"))
      (node (ref "R44") (pin "1") (pinfunction "1_1") (pintype "passive"))
    )
    (net (code "103") (name "Net-(IC9B--IN)") (class "Default")
      (node (ref "IC9") (pin "6") (pinfunction "-IN_6") (pintype "input"))
      (node (ref "R49") (pin "2") (pinfunction "2_2") (pintype "passive"))
      (node (ref "R50") (pin "1") (pinfunction "1_1") (pintype "passive"))
      (node (ref "R54") (pin "2") (pinfunction "2_2") (pintype "passive"))
    )
    (net (code "104") (name "Net-(IC10A-+IN)") (class "Default")
      (node (ref "IC10") (pin "3") (pinfunction "+IN_3") (pintype "input"))
      (node (ref "R60") (pin "2") (pinfunction "2_2") (pintype "passive"))
    )
    (net (code "105") (name "Net-(IC10A--IN)") (class "Default")
      (node (ref "D15") (pin "C") (pinfunction "C_C") (pintype "passive"))
      (node (ref "IC10") (pin "2") (pinfunction "-IN_2") (pintype "input"))
      (node (ref "R62") (pin "2") (pinfunction "2_2") (pintype "passive"))
      (node (ref "R63") (pin "2") (pinfunction "2_2") (pintype "passive"))
      (node (ref "R66") (pin "2") (pinfunction "2_2") (pintype "passive"))
    )
    (net (code "106") (name "Net-(IC10B-+IN)") (class "Default")
      (node (ref "C40") (pin "1") (pinfunction "1_1") (pintype "passive"))
      (node (ref "IC10") (pin "5") (pinfunction "+IN_5") (pintype "input"))
      (node (ref "R31") (pin "2") (pinfunction "2_2") (pintype "passive"))
      (node (ref "R36") (pin "1") (pinfunction "1_1") (pintype "passive"))
    )
    (net (code "107") (name "Net-(IC12A-~{CLR})") (class "Default")
      (node (ref "D16") (pin "A") (pinfunction "A_A") (pintype "passive"))
      (node (ref "D17") (pin "A") (pinfunction "A_A") (pintype "passive"))
      (node (ref "IC12") (pin "6") (pinfunction "~{CLR}_6") (pintype "input"))
      (node (ref "R69") (pin "2") (pinfunction "2_2") (pintype "passive"))
    )
    (net (code "108") (name "Net-(IC15-TRIM{slash}NR)") (class "Default")
      (node (ref "C66") (pin "1") (pinfunction "1_1") (pintype "passive"))
      (node (ref "IC15") (pin "5") (pinfunction "TRIM/NR_5") (pintype "input"))
    )
    (net (code "109") (name "Net-(IC16-VOUTA)") (class "Default")
      (node (ref "IC16") (pin "4") (pinfunction "VOUTA_4") (pintype "output"))
      (node (ref "I_SET") (pin "1") (pinfunction "1_1") (pintype "passive"))
    )
    (net (code "110") (name "Net-(IC16-VOUTB)") (class "Default")
      (node (ref "IC16") (pin "3") (pinfunction "VOUTB_3") (pintype "output"))
      (node (ref "U_SET") (pin "1") (pinfunction "1_1") (pintype "passive"))
    )
    (net (code "111") (name "Net-(IC17-NO)") (class "Default")
      (node (ref "C70") (pin "2") (pinfunction "2_2") (pintype "passive"))
      (node (ref "IC17") (pin "1") (pinfunction "NO_1") (pintype "bidirectional"))
      (node (ref "R74") (pin "1") (pinfunction "1_1") (pintype "passive"))
      (node (ref "ZD2") (pin "3") (pinfunction "C_3") (pintype "passive"))
    )
    (net (code "112") (name "Net-(IC18-AIN0{slash}REFP1)") (class "Default")
      (node (ref "C74") (pin "2") (pinfunction "2_2") (pintype "passive"))
      (node (ref "IC18") (pin "11") (pinfunction "AIN0/REFP1_11") (pintype "input"))
      (node (ref "R78") (pin "2") (pinfunction "2_2") (pintype "passive"))
    )
    (net (code "113") (name "Net-(IC18-AIN1)") (class "Default")
      (node (ref "C71") (pin "2") (pinfunction "2_2") (pintype "passive"))
      (node (ref "IC18") (pin "10") (pinfunction "AIN1_10") (pintype "input"))
      (node (ref "R76") (pin "2") (pinfunction "2_2") (pintype "passive"))
    )
    (net (code "114") (name "Net-(IC18-AIN2)") (class "Default")
      (node (ref "C72") (pin "2") (pinfunction "2_2") (pintype "passive"))
      (node (ref "IC18") (pin "7") (pinfunction "AIN2_7") (pintype "input"))
      (node (ref "R77") (pin "2") (pinfunction "2_2") (pintype "passive"))
    )
    (net (code "115") (name "Net-(IC18-AIN3{slash}REFN1)") (class "Default")
      (node (ref "C73") (pin "1") (pinfunction "1_1") (pintype "passive"))
      (node (ref "IC18") (pin "6") (pinfunction "AIN3/REFN1_6") (pintype "input"))
      (node (ref "R79") (pin "2") (pinfunction "2_2") (pintype "passive"))
    )
    (net (code "116") (name "Net-(IC18-AVDD)") (class "Default")
      (node (ref "C77") (pin "2") (pinfunction "2_2") (pintype "passive"))
      (node (ref "C78") (pin "2") (pinfunction "2_2") (pintype "passive"))
      (node (ref "IC18") (pin "12") (pinfunction "AVDD_12") (pintype "power_in"))
      (node (ref "R80") (pin "2") (pinfunction "2_2") (pintype "passive"))
    )
    (net (code "117") (name "Net-(IC19A-+IN)") (class "Default")
      (node (ref "IC19") (pin "7") (pinfunction "+IN_7") (pintype "input"))
      (node (ref "IC19") (pin "9") (pinfunction "+IN_9") (pintype "input"))
      (node (ref "R85") (pin "1") (pinfunction "1_1") (pintype "passive"))
      (node (ref "R91") (pin "2") (pinfunction "2_2") (pintype "passive"))
    )
    (net (code "118") (name "Net-(IC19A--IN)") (class "Default")
      (node (ref "IC19") (pin "5") (pinfunction "+IN_5") (pintype "input"))
      (node (ref "IC19") (pin "6") (pinfunction "-IN_6") (pintype "input"))
      (node (ref "R81") (pin "2") (pinfunction "2_2") (pintype "passive"))
    )
    (net (code "119") (name "Net-(IC19A-OUT)") (class "Default")
      (node (ref "IC19") (pin "1") (pinfunction "OUT_1") (pintype "open_collector"))
      (node (ref "IC19") (pin "2") (pinfunction "OUT_2") (pintype "open_collector"))
      (node (ref "R86") (pin "1") (pinfunction "1_1") (pintype "passive"))
    )
    (net (code "120") (name "Net-(IC19B--IN)") (class "Default")
      (node (ref "IC19") (pin "10") (pinfunction "-IN_10") (pintype "input"))
      (node (ref "IC19") (pin "4") (pinfunction "-IN_4") (pintype "input"))
      (node (ref "R96") (pin "1") (pinfunction "1_1") (pintype "passive"))
      (node (ref "R98") (pin "2") (pinfunction "2_2") (pintype "passive"))
    )
    (net (code "121") (name "Net-(IC19C--IN)") (class "Default")
      (node (ref "IC19") (pin "11") (pinfunction "+IN_11") (pintype "input"))
      (node (ref "IC19") (pin "8") (pinfunction "-IN_8") (pintype "input"))
      (node (ref "R100") (pin "2") (pinfunction "2_2") (pintype "passive"))
    )
    (net (code "122") (name "Net-(IC19C-OUT)") (class "Default")
      (node (ref "IC19") (pin "13") (pinfunction "OUT_13") (pintype "open_collector"))
      (node (ref "IC19") (pin "14") (pinfunction "OUT_14") (pintype "open_collector"))
      (node (ref "R99") (pin "1") (pinfunction "1_1") (pintype "passive"))
    )
    (net (code "123") (name "Net-(IC20-+IN)") (class "Default")
      (node (ref "C83") (pin "2") (pinfunction "2_2") (pintype "passive"))
      (node (ref "IC20") (pin "2") (pinfunction "+IN_2") (pintype "input"))
      (node (ref "R82") (pin "2") (pinfunction "2_2") (pintype "passive"))
      (node (ref "R87") (pin "1") (pinfunction "1_1") (pintype "passive"))
    )
    (net (code "124") (name "Net-(IC20--IN)") (class "Default")
      (node (ref "C85") (pin "2") (pinfunction "2_2") (pintype "passive"))
      (node (ref "IC20") (pin "3") (pinfunction "-IN_3") (pintype "input"))
      (node (ref "R93") (pin "2") (pinfunction "2_2") (pintype "passive"))
    )
    (net (code "125") (name "Net-(IC20-OUT)") (class "Default")
      (node (ref "IC20") (pin "7") (pinfunction "OUT_7") (pintype "output"))
      (node (ref "Q18") (pin "1") (pinfunction "G_1") (pintype "passive"))
      (node (ref "R89") (pin "2") (pinfunction "2_2") (pintype "passive"))
    )
    (net (code "126") (name "Net-(IC20-~{LE})") (class "Default")
      (node (ref "IC20") (pin "5") (pinfunction "~{LE}_5") (pintype "input"))
      (node (ref "JP3") (pin "COM") (pinfunction "COM_COM") (pintype "passive"))
    )
    (net (code "127") (name "Net-(JP2-PadNO)") (class "Default")
      (node (ref "JP2") (pin "NO") (pinfunction "NO_NO") (pintype "passive"))
      (node (ref "JP3") (pin "NO") (pinfunction "NO_NO") (pintype "passive"))
    )
    (net (code "128") (name "Net-(K1A--)") (class "Default")
      (node (ref "D21") (pin "A") (pinfunction "A_A") (pintype "passive"))
      (node (ref "K1") (pin "8") (pinfunction "-_8") (pintype "passive"))
      (node (ref "Q23") (pin "3") (pinfunction "D_3") (pintype "passive"))
      (node (ref "R114") (pin "1") (pinfunction "1_1") (pintype "passive"))
    )
    (net (code "129") (name "Net-(K1B-S)") (class "Default")
      (node (ref "K1") (pin "4") (pinfunction "S_4") (pintype "passive"))
      (node (ref "X3") (pin "4") (pinfunction "1_4") (pintype "passive"))
    )
    (net (code "130") (name "Net-(K1C-S)") (class "Default")
      (node (ref "K1") (pin "5") (pinfunction "S_5") (pintype "passive"))
      (node (ref "X3") (pin "5") (pinfunction "1_5") (pintype "passive"))
    )
    (net (code "131") (name "Net-(LED1A-C)") (class "Default")
      (node (ref "LED1") (pin "BC") (pinfunction "C_BC") (pintype "passive"))
      (node (ref "R114") (pin "2") (pinfunction "2_2") (pintype "passive"))
    )
    (net (code "132") (name "Net-(LED1B-C)") (class "Default")
      (node (ref "LED1") (pin "TC") (pinfunction "C_TC") (pintype "passive"))
      (node (ref "R71") (pin "2") (pinfunction "2_2") (pintype "passive"))
    )
    (net (code "133") (name "Net-(LED2-C)") (class "Default")
      (node (ref "LED2") (pin "CC") (pinfunction "C_CC") (pintype "passive"))
      (node (ref "R72") (pin "1") (pinfunction "1_1") (pintype "passive"))
    )
    (net (code "134") (name "Net-(LED3A-C)") (class "Default")
      (node (ref "LED3") (pin "BC") (pinfunction "C_BC") (pintype "passive"))
      (node (ref "R92") (pin "2") (pinfunction "2_2") (pintype "passive"))
    )
    (net (code "135") (name "Net-(LED3B-C)") (class "Default")
      (node (ref "LED3") (pin "TC") (pinfunction "C_TC") (pintype "passive"))
      (node (ref "R88") (pin "1") (pinfunction "1_1") (pintype "passive"))
    )
    (net (code "136") (name "Net-(Q1-G)") (class "Default")
      (node (ref "Q1") (pin "1") (pinfunction "G_1") (pintype "passive"))
      (node (ref "R5") (pin "2") (pinfunction "2_2") (pintype "passive"))
    )
    (net (code "137") (name "Net-(Q3-B)") (class "Default")
      (node (ref "Q3") (pin "1") (pinfunction "B_1") (pintype "passive"))
      (node (ref "R32") (pin "2") (pinfunction "2_2") (pintype "passive"))
    )
    (net (code "138") (name "Net-(Q3-E)") (class "Default")
      (node (ref "Q3") (pin "3") (pinfunction "E_3") (pintype "passive"))
      (node (ref "R27") (pin "2") (pinfunction "2_2") (pintype "passive"))
    )
    (net (code "139") (name "Net-(Q4-B)") (class "Default")
      (node (ref "Q4") (pin "1") (pinfunction "B_1") (pintype "passive"))
      (node (ref "R33") (pin "2") (pinfunction "2_2") (pintype "passive"))
    )
    (net (code "140") (name "Net-(Q4-E)") (class "Default")
      (node (ref "Q4") (pin "3") (pinfunction "E_3") (pintype "passive"))
      (node (ref "R29") (pin "2") (pinfunction "2_2") (pintype "passive"))
    )
    (net (code "141") (name "Net-(Q5-PadB)") (class "Default")
      (node (ref "Q5") (pin "B") (pinfunction "B_B") (pintype "passive"))
      (node (ref "R30") (pin "2") (pinfunction "2_2") (pintype "passive"))
    )
    (net (code "142") (name "Net-(Q6-PadB)") (class "Default")
      (node (ref "Q6") (pin "B") (pinfunction "B_B") (pintype "passive"))
      (node (ref "R37") (pin "2") (pinfunction "2_2") (pintype "passive"))
    )
    (net (code "143") (name "Net-(Q6-PadC)") (class "Default")
      (node (ref "Q6") (pin "C") (pinfunction "C_C") (pintype "passive"))
      (node (ref "R35") (pin "2") (pinfunction "2_2") (pintype "passive"))
    )
    (net (code "144") (name "Net-(Q7-G)") (class "Default")
      (node (ref "D9") (pin "A") (pinfunction "A_A") (pintype "passive"))
      (node (ref "Q5") (pin "C") (pinfunction "C_C") (pintype "passive"))
      (node (ref "Q7") (pin "1") (pinfunction "G_1") (pintype "passive"))
      (node (ref "R34") (pin "2") (pinfunction "2_2") (pintype "passive"))
    )
    (net (code "145") (name "Net-(Q7-S)") (class "Default")
      (node (ref "Q7") (pin "3") (pinfunction "S_3") (pintype "passive"))
      (node (ref "R28") (pin "1") (pinfunction "1_1") (pintype "passive"))
      (node (ref "R30") (pin "1") (pinfunction "1_1") (pintype "passive"))
      (node (ref "R34") (pin "1") (pinfunction "1_1") (pintype "passive"))
    )
    (net (code "146") (name "Net-(Q8-E)") (class "Default")
      (node (ref "Q8") (pin "3") (pinfunction "E_3") (pintype "passive"))
      (node (ref "R42") (pin "1") (pinfunction "1_1") (pintype "passive"))
    )
    (net (code "147") (name "Net-(Q9-B)") (class "Default")
      (node (ref "D11") (pin "A") (pinfunction "A_A") (pintype "passive"))
      (node (ref "D13") (pin "A") (pinfunction "A_A") (pintype "passive"))
      (node (ref "Q9") (pin "1") (pinfunction "B_1") (pintype "passive"))
      (node (ref "Q9B") (pin "1") (pinfunction "B_1") (pintype "passive"))
      (node (ref "R43") (pin "1") (pinfunction "1_1") (pintype "passive"))
    )
    (net (code "148") (name "Net-(Q9-E)") (class "Default")
      (node (ref "Q9") (pin "3") (pinfunction "E_3") (pintype "passive"))
      (node (ref "Q9B") (pin "3") (pinfunction "E_3") (pintype "passive"))
      (node (ref "R52") (pin "2") (pinfunction "2_2") (pintype "passive"))
    )
    (net (code "149") (name "Net-(Q9B-C)") (class "Default")
      (node (ref "Q9") (pin "2") (pinfunction "C_2") (pintype "passive"))
      (node (ref "Q9") (pin "4") (pinfunction "C_4") (pintype "passive"))
      (node (ref "Q9B") (pin "2") (pinfunction "C_2") (pintype "passive"))
      (node (ref "R37") (pin "1") (pinfunction "1_1") (pintype "passive"))
      (node (ref "R38") (pin "1") (pinfunction "1_1") (pintype "passive"))
    )
    (net (code "150") (name "Net-(Q10-D)") (class "Default")
      (node (ref "Q10") (pin "3") (pinfunction "D_3") (pintype "passive"))
      (node (ref "R52") (pin "1") (pinfunction "1_1") (pintype "passive"))
    )
    (net (code "151") (name "Net-(Q11-S-Pad1)") (class "Default")
      (node (ref "Q11") (pin "1") (pinfunction "S_1") (pintype "passive"))
      (node (ref "Q11") (pin "2") (pinfunction "S_2") (pintype "passive"))
      (node (ref "Q11") (pin "3") (pinfunction "S_3") (pintype "passive"))
      (node (ref "R58") (pin "1") (pinfunction "1_1") (pintype "passive"))
      (node (ref "R61") (pin "1") (pinfunction "1_1") (pintype "passive"))
    )
    (net (code "152") (name "Net-(Q12-S-Pad1)") (class "Default")
      (node (ref "Q12") (pin "1") (pinfunction "S_1") (pintype "passive"))
      (node (ref "Q12") (pin "2") (pinfunction "S_2") (pintype "passive"))
      (node (ref "Q12") (pin "3") (pinfunction "S_3") (pintype "passive"))
      (node (ref "R67") (pin "2") (pinfunction "2_2") (pintype "passive"))
    )
    (net (code "153") (name "Net-(Q13-D)") (class "Default")
      (node (ref "Q13") (pin "3") (pinfunction "D_3") (pintype "passive"))
      (node (ref "R73") (pin "2") (pinfunction "2_2") (pintype "passive"))
    )
    (net (code "154") (name "Net-(Q14-PadA2)") (class "Default")
      (node (ref "Q14") (pin "A2") (pinfunction "A2_A2") (pintype "passive"))
      (node (ref "R90") (pin "2") (pinfunction "2_2") (pintype "passive"))
    )
    (net (code "155") (name "Net-(Q14-PadG)") (class "Default")
      (node (ref "Q14") (pin "G") (pinfunction "G_G") (pintype "passive"))
      (node (ref "Q15") (pin "C") (pinfunction "C_C") (pintype "passive"))
      (node (ref "R83") (pin "1") (pinfunction "1_1") (pintype "passive"))
    )
    (net (code "156") (name "Net-(Q15-PadE)") (class "Default")
      (node (ref "Q15") (pin "E") (pinfunction "E_E") (pintype "passive"))
      (node (ref "R95") (pin "2") (pinfunction "2_2") (pintype "passive"))
    )
    (net (code "157") (name "Net-(Q16-D)") (class "Default")
      (node (ref "Q16") (pin "3") (pinfunction "D_3") (pintype "passive"))
      (node (ref "R88") (pin "2") (pinfunction "2_2") (pintype "passive"))
    )
    (net (code "158") (name "Net-(Q17-D)") (class "Default")
      (node (ref "Q17") (pin "3") (pinfunction "D_3") (pintype "passive"))
      (node (ref "R92") (pin "1") (pinfunction "1_1") (pintype "passive"))
    )
    (net (code "159") (name "Net-(Q21-PadB)") (class "Default")
      (node (ref "Q21") (pin "B") (pinfunction "B_B") (pintype "passive"))
      (node (ref "R109") (pin "1") (pinfunction "1_1") (pintype "passive"))
      (node (ref "R112") (pin "2") (pinfunction "2_2") (pintype "passive"))
    )
    (net (code "160") (name "Net-(Q22-PadC)") (class "Default")
      (node (ref "Q22") (pin "C") (pinfunction "C_C") (pintype "passive"))
      (node (ref "R106") (pin "1") (pinfunction "1_1") (pintype "passive"))
    )
    (net (code "161") (name "Net-(R61-Pad2)") (class "Default")
      (node (ref "R61") (pin "2") (pinfunction "2_2") (pintype "passive"))
      (node (ref "R67") (pin "2S") (pinfunction "2S_2S") (pintype "passive"))
    )
    (net (code "162") (name "Net-(R67-Pad1S)") (class "Default")
      (node (ref "R67") (pin "1S") (pinfunction "1S_1S") (pintype "passive"))
      (node (ref "R68") (pin "1") (pinfunction "1_1") (pintype "passive"))
    )
    (net (code "163") (name "Net-(R74-Pad2)") (class "Default")
      (node (ref "R74") (pin "2") (pinfunction "2_2") (pintype "passive"))
      (node (ref "R75") (pin "1") (pinfunction "1_1") (pintype "passive"))
    )
    (net (code "164") (name "Net-(R75-Pad2)") (class "Default")
      (node (ref "R75") (pin "2") (pinfunction "2_2") (pintype "passive"))
      (node (ref "X3") (pin "1") (pinfunction "1_1") (pintype "passive"))
    )
    (net (code "165") (name "Net-(R106-Pad2)") (class "Default")
      (node (ref "R106") (pin "2") (pinfunction "2_2") (pintype "passive"))
      (node (ref "R107") (pin "1") (pinfunction "1_1") (pintype "passive"))
    )
    (net (code "166") (name "OE") (class "Default")
      (node (ref "IC13") (pin "2") (pinfunction "GPB1_2") (pintype "bidirectional"))
      (node (ref "OE") (pin "1") (pinfunction "1_1") (pintype "passive"))
    )
    (net (code "167") (name "OE_GREEN") (class "Default")
      (node (ref "IC13") (pin "7") (pinfunction "GPB6_7") (pintype "bidirectional"))
      (node (ref "LED2") (pin "GREEN") (pinfunction "AG_GREEN") (pintype "passive"))
    )
    (net (code "168") (name "OE_RED") (class "Default")
      (node (ref "IC13") (pin "8") (pinfunction "GPB7_8") (pintype "bidirectional"))
      (node (ref "LED2") (pin "RED") (pinfunction "AR_RED") (pintype "passive"))
    )
    (net (code "169") (name "OE_SYNC") (class "Default")
      (node (ref "IC7") (pin "4") (pinfunction "A2_4") (pintype "input"))
      (node (ref "X2") (pin "6") (pinfunction "1_6") (pintype "passive"))
    )
    (net (code "170") (name "OE_TRIG") (class "Default")
      (node (ref "IC12") (pin "1") (pinfunction "CLK_1") (pintype "input"))
      (node (ref "RN2") (pin "6") (pinfunction "2_6") (pintype "passive"))
    )
    (net (code "171") (name "OUTC+") (class "Default")
      (node (ref "C90") (pin "1") (pinfunction "1_1") (pintype "passive"))
      (node (ref "C91") (pin "+") (pinfunction "+_+") (pintype "passive"))
      (node (ref "C92") (pin "1") (pinfunction "1_1") (pintype "passive"))
      (node (ref "C93") (pin "1") (pinfunction "1_1") (pintype "passive"))
      (node (ref "J2") (pin "1") (pinfunction "1_1") (pintype "passive"))
      (node (ref "J2") (pin "NC1") (pinfunction "1_NC1") (pintype "passive"))
      (node (ref "J2") (pin "NC2") (pinfunction "1_NC2") (pintype "passive"))
      (node (ref "J2") (pin "NC3") (pinfunction "1_NC3") (pintype "passive"))
      (node (ref "J2") (pin "NC4") (pinfunction "1_NC4") (pintype "passive"))
      (node (ref "X4") (pin "1") (pinfunction "1_1") (pintype "passive"))
      (node (ref "X4") (pin "2") (pinfunction "1_2") (pintype "passive"))
      (node (ref "X4") (pin "3") (pinfunction "1_3") (pintype "passive"))
      (node (ref "X4") (pin "4") (pinfunction "1_4") (pintype "passive"))
      (node (ref "X4") (pin "5") (pinfunction "1_5") (pintype "passive"))
    )
    (net (code "172") (name "OUTC-") (class "Default")
      (node (ref "C91") (pin "-") (pinfunction "-_-") (pintype "passive"))
      (node (ref "C92") (pin "2") (pinfunction "2_2") (pintype "passive"))
      (node (ref "C93") (pin "2") (pinfunction "2_2") (pintype "passive"))
      (node (ref "C94") (pin "2") (pinfunction "2_2") (pintype "passive"))
      (node (ref "J3") (pin "1") (pinfunction "1_1") (pintype "passive"))
      (node (ref "J3") (pin "NC1") (pinfunction "1_NC1") (pintype "passive"))
      (node (ref "J3") (pin "NC2") (pinfunction "1_NC2") (pintype "passive"))
      (node (ref "J3") (pin "NC3") (pinfunction "1_NC3") (pintype "passive"))
      (node (ref "J3") (pin "NC4") (pinfunction "1_NC4") (pintype "passive"))
      (node (ref "X4") (pin "16") (pinfunction "1_16") (pintype "passive"))
      (node (ref "X4") (pin "17") (pinfunction "1_17") (pintype "passive"))
      (node (ref "X4") (pin "18") (pinfunction "1_18") (pintype "passive"))
      (node (ref "X4") (pin "19") (pinfunction "1_19") (pintype "passive"))
      (node (ref "X4") (pin "20") (pinfunction "1_20") (pintype "passive"))
    )
    (net (code "173") (name "OUTF+") (class "Default")
      (node (ref "F2") (pin "2") (pinfunction "2_2") (pintype "passive"))
      (node (ref "Q14") (pin "A1") (pinfunction "A1_A1") (pintype "passive"))
      (node (ref "R83") (pin "2") (pinfunction "2_2") (pintype "passive"))
      (node (ref "X4") (pin "10") (pinfunction "1_10") (pintype "passive"))
      (node (ref "X4") (pin "6") (pinfunction "1_6") (pintype "passive"))
      (node (ref "X4") (pin "7") (pinfunction "1_7") (pintype "passive"))
      (node (ref "X4") (pin "8") (pinfunction "1_8") (pintype "passive"))
      (node (ref "X4") (pin "9") (pinfunction "1_9") (pintype "passive"))
    )
    (net (code "174") (name "OVP_EN") (class "Default")
      (node (ref "IC13") (pin "5") (pinfunction "GPB4_5") (pintype "bidirectional"))
      (node (ref "IC20") (pin "6") (pinfunction "~{SHDN}_6") (pintype "input"))
    )
    (net (code "175") (name "OVP_IO") (class "Default")
      (node (ref "IC13") (pin "26") (pinfunction "GPA5_26") (pintype "bidirectional"))
      (node (ref "JP2") (pin "COM") (pinfunction "COM_COM") (pintype "passive"))
    )
    (net (code "176") (name "PE") (class "Default")
      (node (ref "C3") (pin "2") (pinfunction "2_2") (pintype "passive"))
      (node (ref "C4") (pin "1") (pinfunction "1_1") (pintype "passive"))
      (node (ref "C90") (pin "2") (pinfunction "2_2") (pintype "passive"))
      (node (ref "C94") (pin "1") (pinfunction "1_1") (pintype "passive"))
      (node (ref "J1") (pin "1") (pinfunction "P$1_1") (pintype "bidirectional"))
      (node (ref "J1") (pin "2") (pinfunction "P$1_2") (pintype "bidirectional"))
      (node (ref "X3") (pin "3") (pinfunction "1_3") (pintype "passive"))
    )
    (net (code "177") (name "POST_OE") (class "Default")
      (node (ref "IC12") (pin "5") (pinfunction "Q_5") (pintype "output"))
      (node (ref "Q10") (pin "1") (pinfunction "G_1") (pintype "passive"))
      (node (ref "R56") (pin "2") (pinfunction "2_2") (pintype "passive"))
    )
    (net (code "178") (name "POST_OUT+") (class "Default")
      (node (ref "C42") (pin "2") (pinfunction "2_2") (pintype "passive"))
      (node (ref "C47") (pin "1") (pinfunction "1_1") (pintype "passive"))
      (node (ref "C59") (pin "1") (pinfunction "1_1") (pintype "passive"))
      (node (ref "D8") (pin "A") (pinfunction "A_A") (pintype "passive"))
      (node (ref "F1") (pin "1") (pinfunction "1_1") (pintype "passive"))
      (node (ref "Q3") (pin "2") (pinfunction "C_2") (pintype "passive"))
      (node (ref "Q4") (pin "2") (pinfunction "C_2") (pintype "passive"))
      (node (ref "Q5") (pin "E") (pinfunction "E_E") (pintype "passive"))
      (node (ref "R12") (pin "2") (pinfunction "2_2") (pintype "passive"))
      (node (ref "R28") (pin "2") (pinfunction "2_2") (pintype "passive"))
    )
    (net (code "179") (name "POST_OUT-") (class "Default")
      (node (ref "C43") (pin "1") (pinfunction "1_1") (pintype "passive"))
      (node (ref "C44") (pin "2") (pinfunction "2_2") (pintype "passive"))
      (node (ref "C89") (pin "-") (pinfunction "-_-") (pintype "passive"))
      (node (ref "C95") (pin "2") (pinfunction "2_2") (pintype "passive"))
      (node (ref "D14") (pin "A") (pinfunction "A_A") (pintype "passive"))
      (node (ref "D20") (pin "1") (pinfunction "A_1") (pintype "passive"))
      (node (ref "D20") (pin "2") (pinfunction "A_2") (pintype "passive"))
      (node (ref "JP5") (pin "1") (pinfunction "1_1") (pintype "passive"))
      (node (ref "K1") (pin "7") (pinfunction "O_7") (pintype "passive"))
      (node (ref "Q11") (pin "MB") (pinfunction "D_MB") (pintype "passive"))
      (node (ref "Q12") (pin "MB") (pinfunction "D_MB") (pintype "passive"))
      (node (ref "Q22") (pin "E") (pinfunction "E_E") (pintype "passive"))
      (node (ref "R110") (pin "1") (pinfunction "1_1") (pintype "passive"))
      (node (ref "R113") (pin "1") (pinfunction "1_1") (pintype "passive"))
      (node (ref "X4") (pin "11") (pinfunction "1_11") (pintype "passive"))
      (node (ref "X4") (pin "12") (pinfunction "1_12") (pintype "passive"))
      (node (ref "X4") (pin "13") (pinfunction "1_13") (pintype "passive"))
      (node (ref "X4") (pin "14") (pinfunction "1_14") (pintype "passive"))
      (node (ref "X4") (pin "15") (pinfunction "1_15") (pintype "passive"))
    )
    (net (code "180") (name "PREG_IN-") (class "Default")
      (node (ref "C10") (pin "2") (pinfunction "2_2") (pintype "passive"))
      (node (ref "C11") (pin "-") (pinfunction "-_-") (pintype "passive"))
      (node (ref "C15") (pin "2") (pinfunction "2_2") (pintype "passive"))
      (node (ref "C16") (pin "-") (pinfunction "-_-") (pintype "passive"))
      (node (ref "C2") (pin "-") (pinfunction "-_-") (pintype "passive"))
      (node (ref "C3") (pin "1") (pinfunction "1_1") (pintype "passive"))
      (node (ref "C5") (pin "2") (pinfunction "2_2") (pintype "passive"))
      (node (ref "C6") (pin "2") (pinfunction "2_2") (pintype "passive"))
      (node (ref "C7") (pin "2") (pinfunction "2_2") (pintype "passive"))
      (node (ref "D2") (pin "1") (pinfunction "A_1") (pintype "passive"))
      (node (ref "D2") (pin "2") (pinfunction "A_2") (pintype "passive"))
      (node (ref "IC1") (pin "TP") (pinfunction "PGND_TP") (pintype "passive"))
      (node (ref "L1") (pin "4") (pinfunction "2_4") (pintype "passive"))
      (node (ref "R2") (pin "1") (pinfunction "1_1") (pintype "passive"))
      (node (ref "R7") (pin "1") (pinfunction "1_1") (pintype "passive"))
      (node (ref "SH1") (pin "1") (pinfunction "GND_A_1") (pintype "bidirectional"))
      (node (ref "SH2") (pin "2") (pinfunction "GND_B_2") (pintype "bidirectional"))
      (node (ref "SH3") (pin "2") (pinfunction "GND_B_2") (pintype "bidirectional"))
      (node (ref "ZD1") (pin "A") (pinfunction "A_A") (pintype "passive"))
    )
    (net (code "181") (name "PREG_OUT+") (class "Default")
      (node (ref "C13") (pin "+") (pinfunction "+_+") (pintype "passive"))
      (node (ref "C14") (pin "1") (pinfunction "1_1") (pintype "passive"))
      (node (ref "L3") (pin "2") (pinfunction "2_2") (pintype "passive"))
      (node (ref "R27") (pin "1") (pinfunction "1_1") (pintype "passive"))
      (node (ref "R29") (pin "1") (pinfunction "1_1") (pintype "passive"))
      (node (ref "R6") (pin "2") (pinfunction "2_2") (pintype "passive"))
    )
    (net (code "182") (name "PREG_OUT-") (class "Default")
      (node (ref "C13") (pin "-") (pinfunction "-_-") (pintype "passive"))
      (node (ref "C14") (pin "2") (pinfunction "2_2") (pintype "passive"))
      (node (ref "D14") (pin "C") (pinfunction "C_C") (pintype "passive"))
      (node (ref "Q7") (pin "2") (pinfunction "D_2") (pintype "passive"))
      (node (ref "R67") (pin "1") (pinfunction "1_1") (pintype "passive"))
      (node (ref "R90") (pin "1") (pinfunction "1_1") (pintype "passive"))
      (node (ref "SH2") (pin "1") (pinfunction "GND_A_1") (pintype "bidirectional"))
    )
    (net (code "183") (name "PRE_OE") (class "Default")
      (node (ref "D1") (pin "A") (pinfunction "A_A") (pintype "passive"))
      (node (ref "IC12") (pin "2") (pinfunction "D_2") (pintype "input"))
      (node (ref "OE") (pin "2") (pinfunction "2_2") (pintype "passive"))
    )
    (net (code "184") (name "PWRGOOD") (class "Default")
      (node (ref "IC13") (pin "24") (pinfunction "GPA3_24") (pintype "bidirectional"))
      (node (ref "IC2") (pin "6") (pinfunction "PWRGD_6") (pintype "output"))
      (node (ref "R19") (pin "2") (pinfunction "2_2") (pintype "passive"))
    )
    (net (code "185") (name "RSENSE") (class "Default")
      (node (ref "IC13") (pin "3") (pinfunction "GPB2_3") (pintype "bidirectional"))
      (node (ref "Q23") (pin "1") (pinfunction "G_1") (pintype "passive"))
      (node (ref "R115") (pin "2") (pinfunction "2_2") (pintype "passive"))
    )
    (net (code "186") (name "SCLK") (class "Default")
      (node (ref "IC13") (pin "12") (pinfunction "SCK_12") (pintype "input"))
      (node (ref "IC14") (pin "3") (pinfunction "SCLK_3") (pintype "input"))
      (node (ref "IC16") (pin "6") (pinfunction "SCLK_6") (pintype "input"))
      (node (ref "IC18") (pin "1") (pinfunction "SCLK_1") (pintype "input"))
      (node (ref "RN1") (pin "5") (pinfunction "2_5") (pintype "passive"))
    )
    (net (code "187") (name "SENSE+") (class "Default")
      (node (ref "C41") (pin "1") (pinfunction "1_1") (pintype "passive"))
      (node (ref "JP4") (pin "1") (pinfunction "1_1") (pintype "passive"))
      (node (ref "K1") (pin "3") (pinfunction "P_3") (pintype "passive"))
      (node (ref "R105") (pin "1") (pinfunction "1_1") (pintype "passive"))
      (node (ref "R45") (pin "2") (pinfunction "2_2") (pintype "passive"))
    )
    (net (code "188") (name "SENSE-") (class "Default")
      (node (ref "C46") (pin "1") (pinfunction "1_1") (pintype "passive"))
      (node (ref "JP5") (pin "2") (pinfunction "2_2") (pintype "passive"))
      (node (ref "K1") (pin "6") (pinfunction "P_6") (pintype "passive"))
      (node (ref "R111") (pin "2") (pinfunction "2_2") (pintype "passive"))
      (node (ref "R51") (pin "2") (pinfunction "2_2") (pintype "passive"))
    )
    (net (code "189") (name "SENSE_ERR") (class "Default")
      (node (ref "IC13") (pin "21") (pinfunction "GPA0_21") (pintype "bidirectional"))
      (node (ref "Q21") (pin "C") (pinfunction "C_C") (pintype "passive"))
      (node (ref "R108") (pin "1") (pinfunction "1_1") (pintype "passive"))
    )
    (net (code "190") (name "SENSE_PROT") (class "Default")
      (node (ref "D17") (pin "C") (pinfunction "C_C") (pintype "passive"))
      (node (ref "Q19") (pin "C") (pinfunction "C_C") (pintype "passive"))
    )
    (net (code "191") (name "SGND") (class "Default")
      (node (ref "C17") (pin "2") (pinfunction "2_2") (pintype "passive"))
      (node (ref "C18") (pin "2") (pinfunction "2_2") (pintype "passive"))
      (node (ref "C9") (pin "1") (pinfunction "1_1") (pintype "passive"))
      (node (ref "IC1") (pin "3") (pinfunction "SGND_3") (pintype "passive"))
      (node (ref "R13") (pin "2") (pinfunction "2_2") (pintype "passive"))
      (node (ref "R4") (pin "2") (pinfunction "2_2") (pintype "passive"))
      (node (ref "SH3") (pin "1") (pinfunction "GND_A_1") (pintype "bidirectional"))
    )
    (net (code "192") (name "U_MON") (class "Default")
      (node (ref "IC9") (pin "7") (pinfunction "OUT_7") (pintype "output"))
      (node (ref "R48") (pin "1") (pinfunction "1_1") (pintype "passive"))
      (node (ref "R49") (pin "1") (pinfunction "1_1") (pintype "passive"))
      (node (ref "R78") (pin "1") (pinfunction "1_1") (pintype "passive"))
      (node (ref "R82") (pin "1") (pinfunction "1_1") (pintype "passive"))
    )
    (net (code "193") (name "U_SERVO") (class "Default")
      (node (ref "C45") (pin "2") (pinfunction "2_2") (pintype "passive"))
      (node (ref "D11") (pin "C") (pinfunction "C_C") (pintype "passive"))
      (node (ref "D12") (pin "A") (pinfunction "A_A") (pintype "passive"))
      (node (ref "IC9") (pin "1") (pinfunction "OUT_1") (pintype "output"))
      (node (ref "R81") (pin "1") (pinfunction "1_1") (pintype "passive"))
    )
    (net (code "194") (name "U_SET") (class "Default")
      (node (ref "IC17") (pin "3") (pinfunction "NC_3") (pintype "bidirectional"))
      (node (ref "JP1") (pin "1") (pinfunction "1_1") (pintype "passive"))
      (node (ref "R77") (pin "1") (pinfunction "1_1") (pintype "passive"))
      (node (ref "R93") (pin "1") (pinfunction "1_1") (pintype "passive"))
      (node (ref "U_SET") (pin "2") (pinfunction "2_2") (pintype "passive"))
    )
    (net (code "195") (name "U_SET_OUT") (class "Default")
      (node (ref "IC17") (pin "4") (pinfunction "COM_4") (pintype "bidirectional"))
      (node (ref "JP1") (pin "2") (pinfunction "2_2") (pintype "passive"))
      (node (ref "R47") (pin "1") (pinfunction "1_1") (pintype "passive"))
    )
    (net (code "196") (name "V+") (class "Default")
      (node (ref "C48") (pin "2") (pinfunction "2_2") (pintype "passive"))
      (node (ref "C49") (pin "1") (pinfunction "1_1") (pintype "passive"))
      (node (ref "C50") (pin "2") (pinfunction "2_2") (pintype "passive"))
      (node (ref "C51") (pin "2") (pinfunction "2_2") (pintype "passive"))
      (node (ref "C52") (pin "2") (pinfunction "2_2") (pintype "passive"))
      (node (ref "C62") (pin "1") (pinfunction "1_1") (pintype "passive"))
      (node (ref "C65") (pin "1") (pinfunction "1_1") (pintype "passive"))
      (node (ref "C67") (pin "2") (pinfunction "2_2") (pintype "passive"))
      (node (ref "C69") (pin "1") (pinfunction "1_1") (pintype "passive"))
      (node (ref "C80") (pin "2") (pinfunction "2_2") (pintype "passive"))
      (node (ref "C81") (pin "1") (pinfunction "1_1") (pintype "passive"))
      (node (ref "C82") (pin "2") (pinfunction "2_2") (pintype "passive"))
      (node (ref "FB1") (pin "P$2") (pinfunction "2_P$2") (pintype "passive"))
      (node (ref "IC10") (pin "8") (pinfunction "V+_8") (pintype "power_in"))
      (node (ref "IC11") (pin "7") (pinfunction "V+_7") (pintype "power_in"))
      (node (ref "IC15") (pin "2") (pinfunction "VIN_2") (pintype "passive"))
      (node (ref "IC16") (pin "1") (pinfunction "VDD_1") (pintype "power_in"))
      (node (ref "IC17") (pin "5") (pinfunction "VDD_5") (pintype "power_in"))
      (node (ref "IC19") (pin "3") (pinfunction "V+_3") (pintype "power_in"))
      (node (ref "IC20") (pin "1") (pinfunction "+VCC_1") (pintype "passive"))
      (node (ref "IC9") (pin "8") (pinfunction "V+_8") (pintype "power_in"))
      (node (ref "JP3") (pin "NC") (pinfunction "NC_NC") (pintype "passive"))
      (node (ref "R101") (pin "1") (pinfunction "1_1") (pintype "passive"))
      (node (ref "R43") (pin "2") (pinfunction "2_2") (pintype "passive"))
      (node (ref "R80") (pin "1") (pinfunction "1_1") (pintype "passive"))
      (node (ref "R85") (pin "2") (pinfunction "2_2") (pintype "passive"))
    )
    (net (code "197") (name "V-") (class "Default")
      (node (ref "C53") (pin "2") (pinfunction "2_2") (pintype "passive"))
      (node (ref "C55") (pin "2") (pinfunction "2_2") (pintype "passive"))
      (node (ref "C56") (pin "1") (pinfunction "1_1") (pintype "passive"))
      (node (ref "C57") (pin "2") (pinfunction "2_2") (pintype "passive"))
      (node (ref "C58") (pin "2") (pinfunction "2_2") (pintype "passive"))
      (node (ref "C84") (pin "2") (pinfunction "2_2") (pintype "passive"))
      (node (ref "FB3") (pin "P$2") (pinfunction "2_P$2") (pintype "passive"))
      (node (ref "IC10") (pin "4") (pinfunction "V-_4") (pintype "power_in"))
      (node (ref "IC11") (pin "4") (pinfunction "V-_4") (pintype "power_in"))
      (node (ref "IC19") (pin "12") (pinfunction "GND_12") (pintype "power_in"))
      (node (ref "IC9") (pin "4") (pinfunction "V-_4") (pintype "power_in"))
      (node (ref "R98") (pin "1") (pinfunction "1_1") (pintype "passive"))
    )
    (net (code "198") (name "unconnected-(IC1-PGOOD-Pad7)") (class "Default")
      (node (ref "IC1") (pin "7") (pinfunction "PGOOD_7") (pintype "output"))
    )
    (net (code "199") (name "unconnected-(IC1-PLLIN{slash}MODE-Pad1)") (class "Default")
      (node (ref "IC1") (pin "1") (pinfunction "PLLIN/MODE_1") (pintype "input"))
    )
    (net (code "200") (name "unconnected-(IC4-Y3-Pad3)") (class "Default")
      (node (ref "IC4") (pin "3") (pinfunction "Y3_3") (pintype "output"))
    )
    (net (code "201") (name "unconnected-(IC12A-~{Q}-Pad3)") (class "Default")
      (node (ref "IC12") (pin "3") (pinfunction "~{Q}_3") (pintype "output"))
    )
    (net (code "202") (name "unconnected-(IC13-INTB-Pad19)") (class "Default")
      (node (ref "IC13") (pin "19") (pinfunction "INTB_19") (pintype "output"))
    )
    (net (code "203") (name "unconnected-(IC15-TEMP-Pad3)") (class "Default")
      (node (ref "IC15") (pin "3") (pinfunction "TEMP_3") (pintype "input"))
    )
    (net (code "204") (name "~{ADC_DRDY}") (class "Default")
      (node (ref "IC13") (pin "25") (pinfunction "GPA4_25") (pintype "bidirectional"))
      (node (ref "IC18") (pin "14") (pinfunction "~{DRDY}_14") (pintype "output"))
    )
    (net (code "205") (name "~{DP_DRIVE}") (class "Default")
      (node (ref "Q8") (pin "1") (pinfunction "B_1") (pintype "passive"))
      (node (ref "R39") (pin "1") (pinfunction "1_1") (pintype "passive"))
      (node (ref "R73") (pin "1") (pinfunction "1_1") (pintype "passive"))
    )
    (net (code "206") (name "~{OVP_FAULT}") (class "Default")
      (node (ref "D16") (pin "C") (pinfunction "C_C") (pintype "passive"))
      (node (ref "JP2") (pin "NC") (pinfunction "NC_NC") (pintype "passive"))
      (node (ref "Q18") (pin "3") (pinfunction "D_3") (pintype "passive"))
      (node (ref "R101") (pin "2") (pinfunction "2_2") (pintype "passive"))
    )
    (net (code "207") (name "~{RESET}") (class "Default")
      (node (ref "IC13") (pin "18") (pinfunction "~{RESET}_18") (pintype "input"))
      (node (ref "IC7") (pin "12") (pinfunction "B3_12") (pintype "output"))
    )
    (net (code "208") (name "~{SET_DP}") (class "Default")
      (node (ref "IC13") (pin "1") (pinfunction "GPB0_1") (pintype "bidirectional"))
      (node (ref "Q13") (pin "1") (pinfunction "G_1") (pintype "passive"))
      (node (ref "R70") (pin "2") (pinfunction "2_2") (pintype "passive"))
    )
    (net (code "209") (name "~{TEMP_CS}") (class "Default")
      (node (ref "IC13") (pin "6") (pinfunction "GPB5_6") (pintype "bidirectional"))
      (node (ref "IC14") (pin "1") (pinfunction "~{CS}_1") (pintype "input"))
    )
  )
)
